# ELC0102_-_Red_Digits.net
KiCad netlist of a schematic drawn in Altium Designer
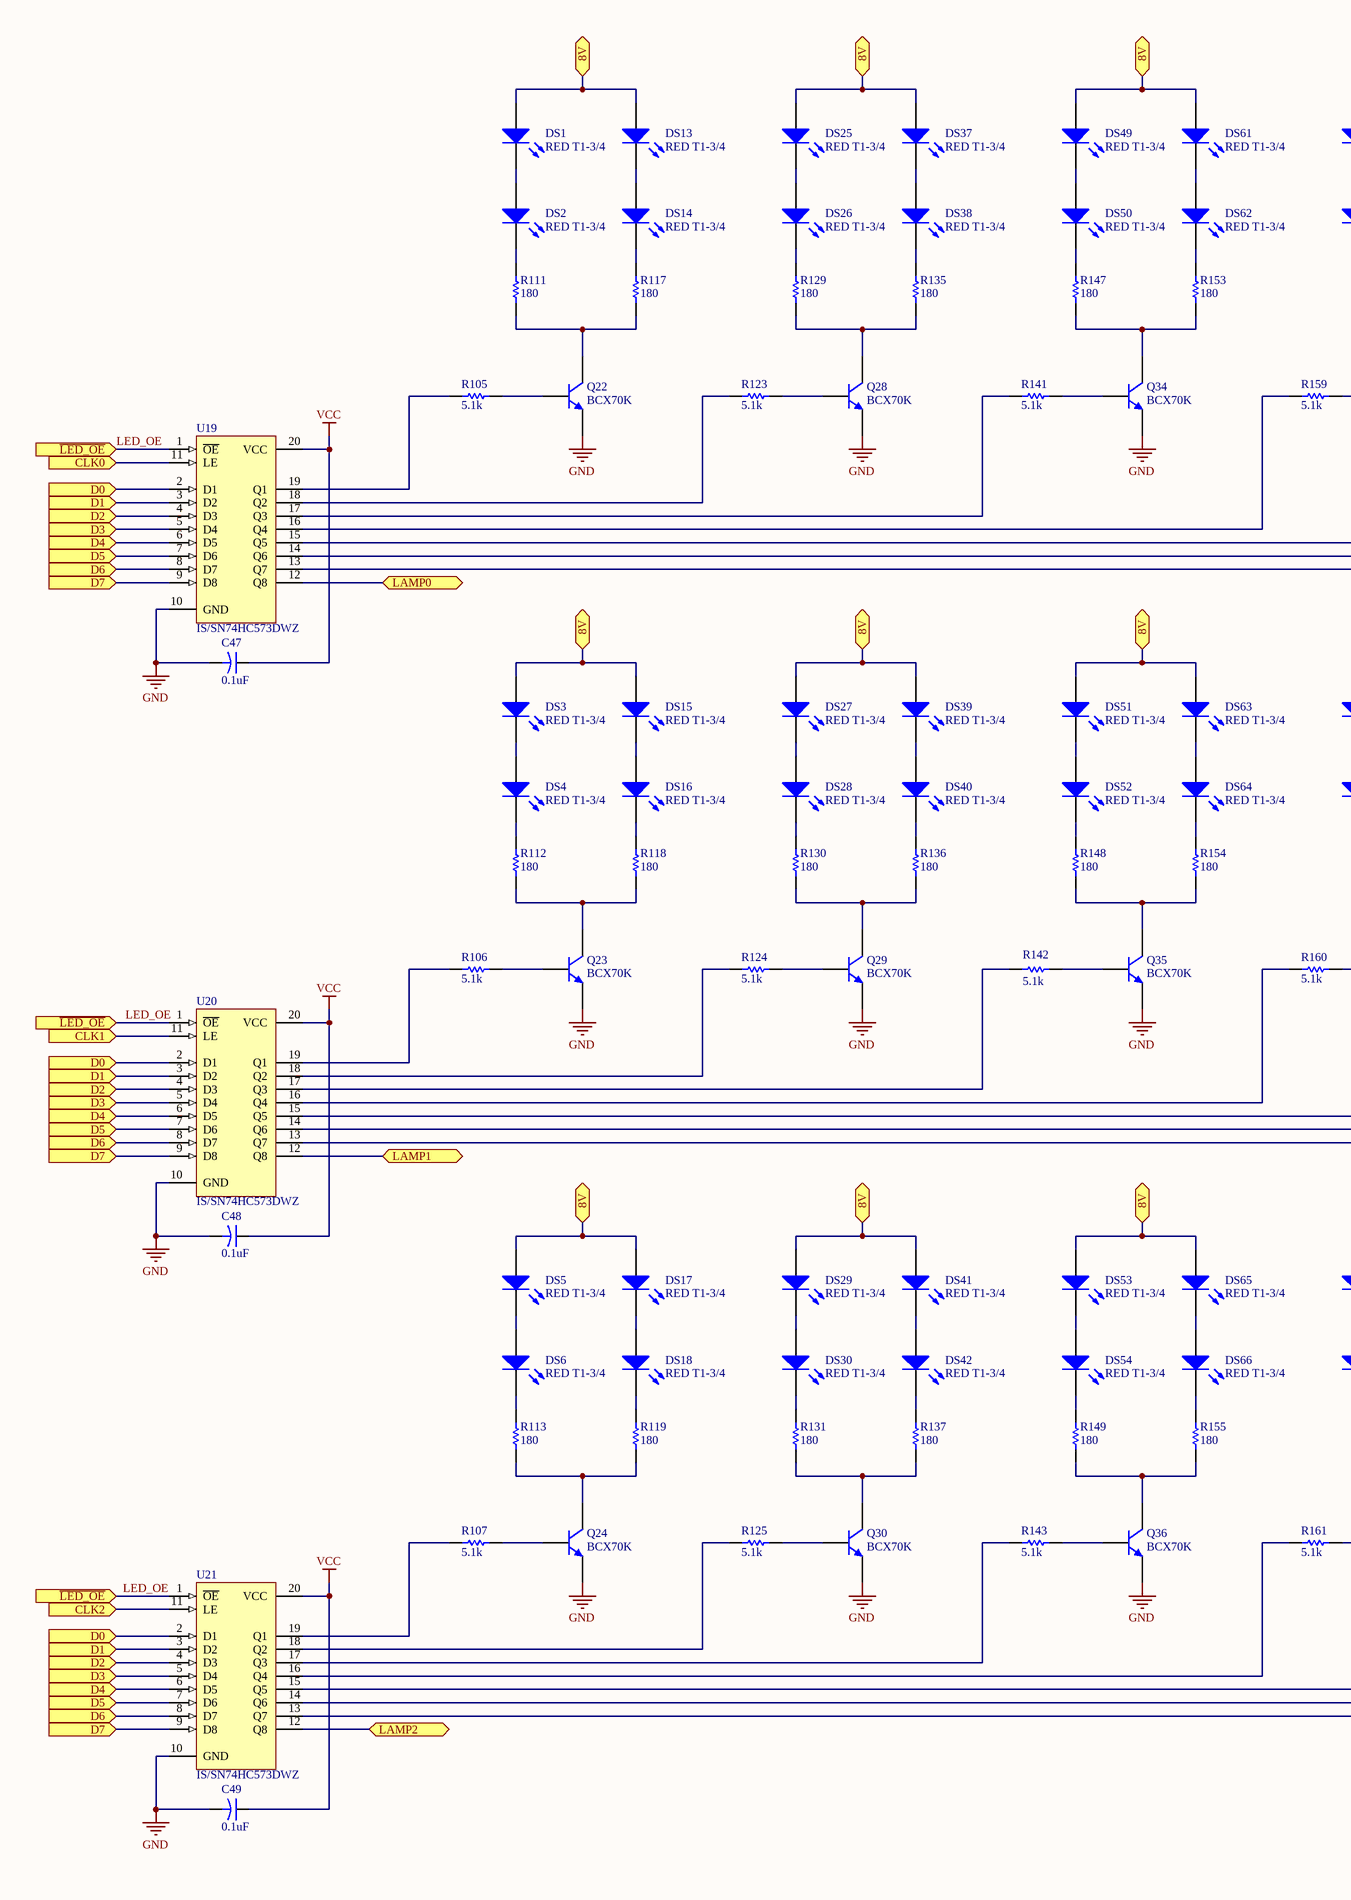
[diagram p0: ELC0102 - Red Digits.SchDoc, left]
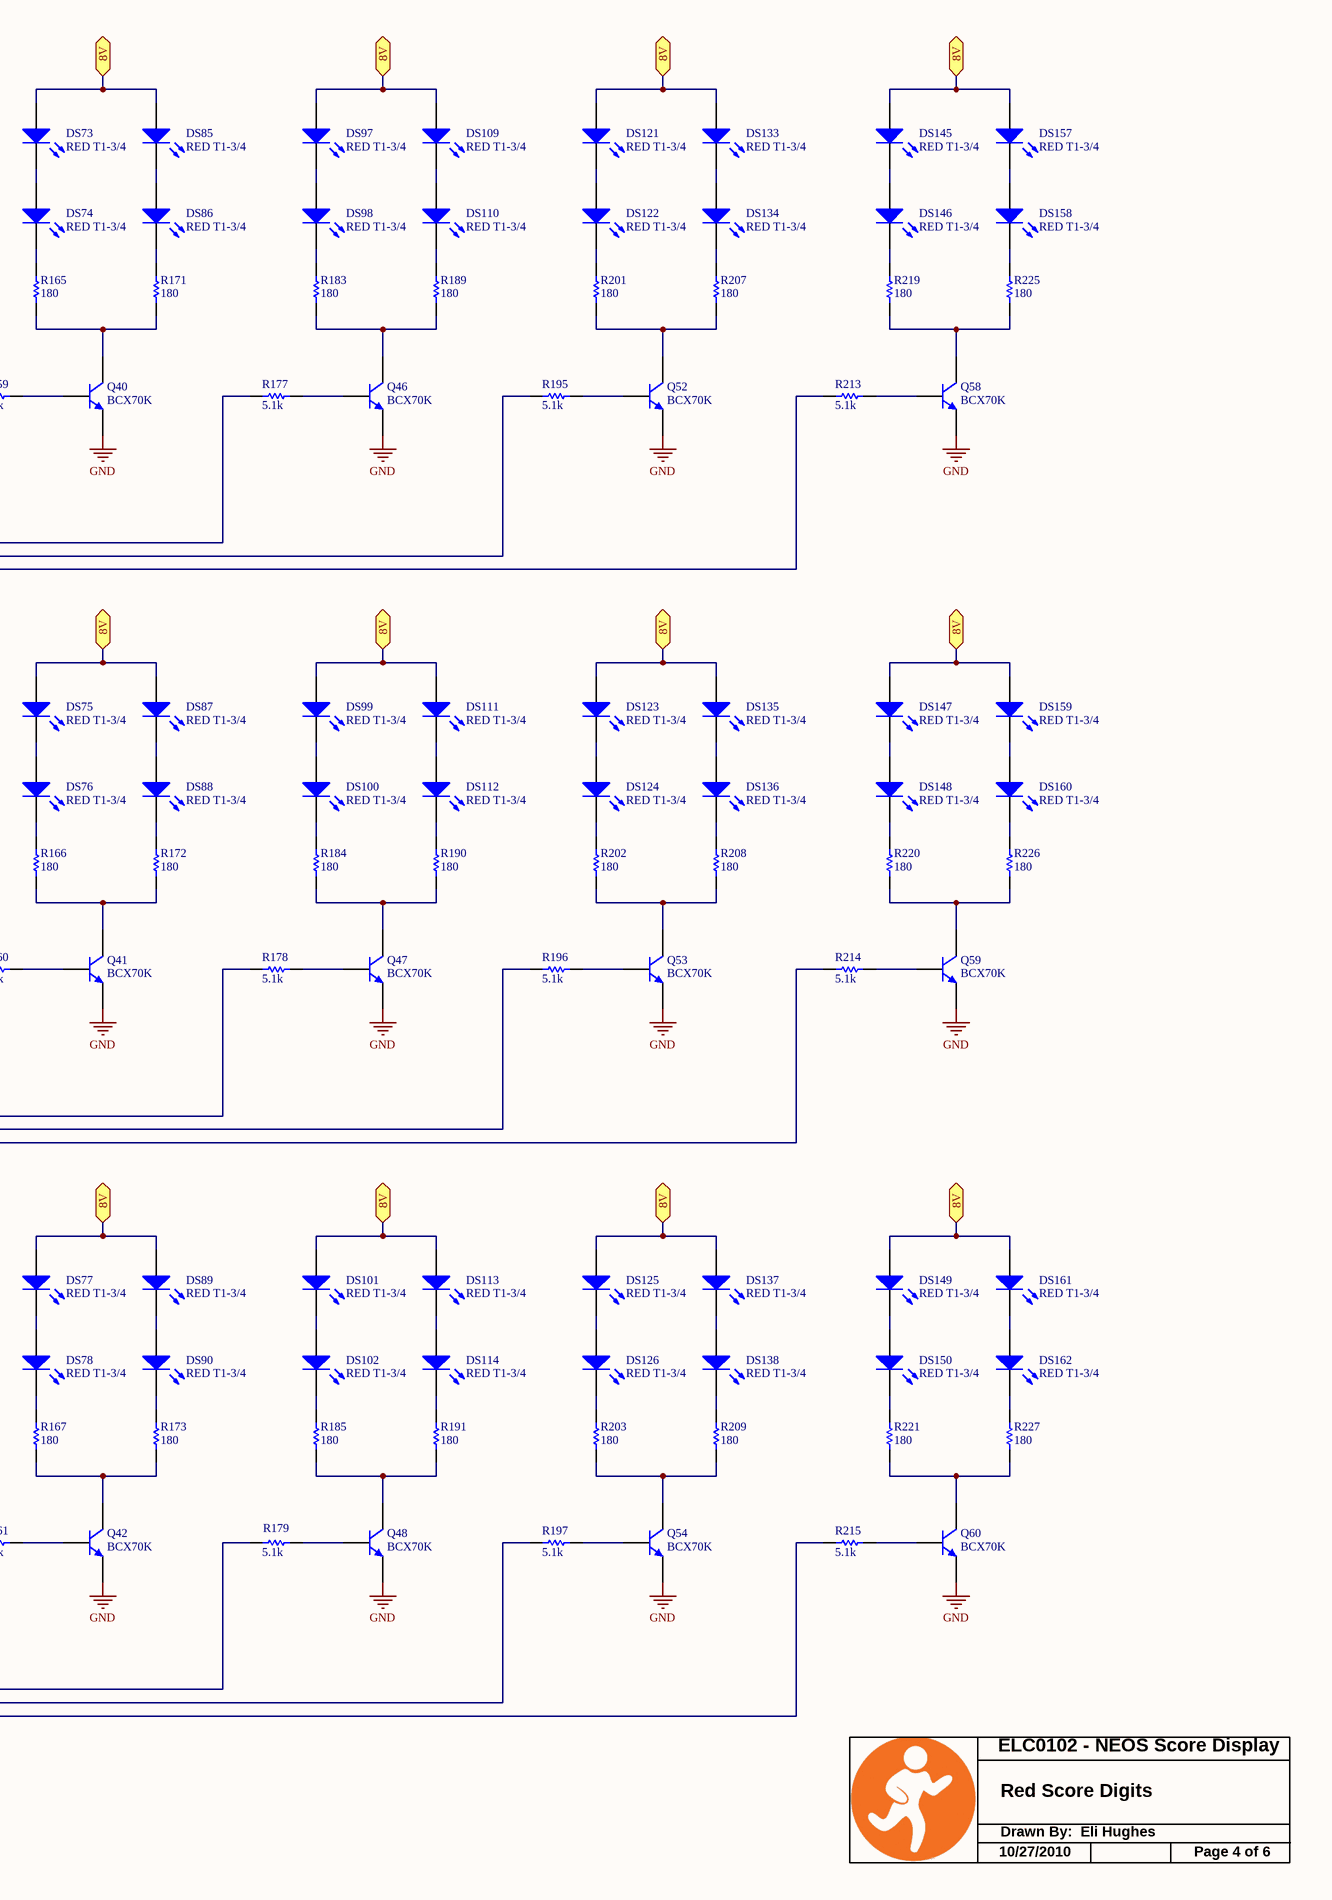
[diagram p1: ELC0102 - Red Digits.SchDoc, right]

(export (version "E")
  (design (tool "Eeschema 10.0.6"))
  (components
    (comp (ref "C47")
      (value "0.1uF")
      (footprint "C0805")
      (description "CAP .10UF 50V CERAMIC X7R 0805")
      (fields
        (field (name "MANUFACTURER") "Kemet")
        (field (name "MANUFACTURER PART NUMBER") "C0805C104K5RACTU")
        (field (name "SOURCE") "Digikey")
      )
      (libsource (lib "ELC102 - Scoreboard") (part "CS/C0805C104K5RACK"))
    )
    (comp (ref "C48")
      (value "0.1uF")
      (footprint "C0805")
      (description "CAP .10UF 50V CERAMIC X7R 0805")
      (fields
        (field (name "MANUFACTURER") "Kemet")
        (field (name "MANUFACTURER PART NUMBER") "C0805C104K5RACTU")
        (field (name "SOURCE") "Digikey")
      )
      (libsource (lib "ELC102 - Scoreboard") (part "CS/C0805C104K5RACK"))
    )
    (comp (ref "C49")
      (value "0.1uF")
      (footprint "C0805")
      (description "CAP .10UF 50V CERAMIC X7R 0805")
      (fields
        (field (name "MANUFACTURER") "Kemet")
        (field (name "MANUFACTURER PART NUMBER") "C0805C104K5RACTU")
        (field (name "SOURCE") "Digikey")
      )
      (libsource (lib "ELC102 - Scoreboard") (part "CS/C0805C104K5RACK"))
    )
    (comp (ref "DS1")
      (value "RED T1-3/4")
      (footprint "LED T1-3/4 Flush")
      (description "Optek LED Red /Clear High Brightness T1-3/4")
      (fields
        (field (name "MANUFACTURER") "TT Electronics/Optek Technology")
        (field (name "MANUFACTURER PART NUMBER") "OVLFR3C7")
        (field (name "SOURCE") "Digikey")
      )
      (libsource (lib "ScoreBoard") (part "LRCOVLFR3C7Z"))
    )
    (comp (ref "DS2")
      (value "RED T1-3/4")
      (footprint "LED T1-3/4 Flush")
      (description "Optek LED Red /Clear High Brightness T1-3/4")
      (fields
        (field (name "MANUFACTURER") "TT Electronics/Optek Technology")
        (field (name "MANUFACTURER PART NUMBER") "OVLFR3C7")
        (field (name "SOURCE") "Digikey")
      )
      (libsource (lib "ScoreBoard") (part "LRCOVLFR3C7Z"))
    )
    (comp (ref "DS3")
      (value "RED T1-3/4")
      (footprint "LED T1-3/4 Flush")
      (description "Optek LED Red /Clear High Brightness T1-3/4")
      (fields
        (field (name "MANUFACTURER") "TT Electronics/Optek Technology")
        (field (name "MANUFACTURER PART NUMBER") "OVLFR3C7")
        (field (name "SOURCE") "Digikey")
      )
      (libsource (lib "ScoreBoard") (part "LRCOVLFR3C7Z"))
    )
    (comp (ref "DS4")
      (value "RED T1-3/4")
      (footprint "LED T1-3/4 Flush")
      (description "Optek LED Red /Clear High Brightness T1-3/4")
      (fields
        (field (name "MANUFACTURER") "TT Electronics/Optek Technology")
        (field (name "MANUFACTURER PART NUMBER") "OVLFR3C7")
        (field (name "SOURCE") "Digikey")
      )
      (libsource (lib "ScoreBoard") (part "LRCOVLFR3C7Z"))
    )
    (comp (ref "DS5")
      (value "RED T1-3/4")
      (footprint "LED T1-3/4 Flush")
      (description "Optek LED Red /Clear High Brightness T1-3/4")
      (fields
        (field (name "MANUFACTURER") "TT Electronics/Optek Technology")
        (field (name "MANUFACTURER PART NUMBER") "OVLFR3C7")
        (field (name "SOURCE") "Digikey")
      )
      (libsource (lib "ScoreBoard") (part "LRCOVLFR3C7Z"))
    )
    (comp (ref "DS6")
      (value "RED T1-3/4")
      (footprint "LED T1-3/4 Flush")
      (description "Optek LED Red /Clear High Brightness T1-3/4")
      (fields
        (field (name "MANUFACTURER") "TT Electronics/Optek Technology")
        (field (name "MANUFACTURER PART NUMBER") "OVLFR3C7")
        (field (name "SOURCE") "Digikey")
      )
      (libsource (lib "ScoreBoard") (part "LRCOVLFR3C7Z"))
    )
    (comp (ref "DS13")
      (value "RED T1-3/4")
      (footprint "LED T1-3/4 Flush")
      (description "Optek LED Red /Clear High Brightness T1-3/4")
      (fields
        (field (name "MANUFACTURER") "TT Electronics/Optek Technology")
        (field (name "MANUFACTURER PART NUMBER") "OVLFR3C7")
        (field (name "SOURCE") "Digikey")
      )
      (libsource (lib "ScoreBoard") (part "LRCOVLFR3C7Z"))
    )
    (comp (ref "DS14")
      (value "RED T1-3/4")
      (footprint "LED T1-3/4 Flush")
      (description "Optek LED Red /Clear High Brightness T1-3/4")
      (fields
        (field (name "MANUFACTURER") "TT Electronics/Optek Technology")
        (field (name "MANUFACTURER PART NUMBER") "OVLFR3C7")
        (field (name "SOURCE") "Digikey")
      )
      (libsource (lib "ScoreBoard") (part "LRCOVLFR3C7Z"))
    )
    (comp (ref "DS15")
      (value "RED T1-3/4")
      (footprint "LED T1-3/4 Flush")
      (description "Optek LED Red /Clear High Brightness T1-3/4")
      (fields
        (field (name "MANUFACTURER") "TT Electronics/Optek Technology")
        (field (name "MANUFACTURER PART NUMBER") "OVLFR3C7")
        (field (name "SOURCE") "Digikey")
      )
      (libsource (lib "ScoreBoard") (part "LRCOVLFR3C7Z"))
    )
    (comp (ref "DS16")
      (value "RED T1-3/4")
      (footprint "LED T1-3/4 Flush")
      (description "Optek LED Red /Clear High Brightness T1-3/4")
      (fields
        (field (name "MANUFACTURER") "TT Electronics/Optek Technology")
        (field (name "MANUFACTURER PART NUMBER") "OVLFR3C7")
        (field (name "SOURCE") "Digikey")
      )
      (libsource (lib "ScoreBoard") (part "LRCOVLFR3C7Z"))
    )
    (comp (ref "DS17")
      (value "RED T1-3/4")
      (footprint "LED T1-3/4 Flush")
      (description "Optek LED Red /Clear High Brightness T1-3/4")
      (fields
        (field (name "MANUFACTURER") "TT Electronics/Optek Technology")
        (field (name "MANUFACTURER PART NUMBER") "OVLFR3C7")
        (field (name "SOURCE") "Digikey")
      )
      (libsource (lib "ScoreBoard") (part "LRCOVLFR3C7Z"))
    )
    (comp (ref "DS18")
      (value "RED T1-3/4")
      (footprint "LED T1-3/4 Flush")
      (description "Optek LED Red /Clear High Brightness T1-3/4")
      (fields
        (field (name "MANUFACTURER") "TT Electronics/Optek Technology")
        (field (name "MANUFACTURER PART NUMBER") "OVLFR3C7")
        (field (name "SOURCE") "Digikey")
      )
      (libsource (lib "ScoreBoard") (part "LRCOVLFR3C7Z"))
    )
    (comp (ref "DS25")
      (value "RED T1-3/4")
      (footprint "LED T1-3/4 Flush")
      (description "Optek LED Red /Clear High Brightness T1-3/4")
      (fields
        (field (name "MANUFACTURER") "TT Electronics/Optek Technology")
        (field (name "MANUFACTURER PART NUMBER") "OVLFR3C7")
        (field (name "SOURCE") "Digikey")
      )
      (libsource (lib "ScoreBoard") (part "LRCOVLFR3C7Z"))
    )
    (comp (ref "DS26")
      (value "RED T1-3/4")
      (footprint "LED T1-3/4 Flush")
      (description "Optek LED Red /Clear High Brightness T1-3/4")
      (fields
        (field (name "MANUFACTURER") "TT Electronics/Optek Technology")
        (field (name "MANUFACTURER PART NUMBER") "OVLFR3C7")
        (field (name "SOURCE") "Digikey")
      )
      (libsource (lib "ScoreBoard") (part "LRCOVLFR3C7Z"))
    )
    (comp (ref "DS27")
      (value "RED T1-3/4")
      (footprint "LED T1-3/4 Flush")
      (description "Optek LED Red /Clear High Brightness T1-3/4")
      (fields
        (field (name "MANUFACTURER") "TT Electronics/Optek Technology")
        (field (name "MANUFACTURER PART NUMBER") "OVLFR3C7")
        (field (name "SOURCE") "Digikey")
      )
      (libsource (lib "ScoreBoard") (part "LRCOVLFR3C7Z"))
    )
    (comp (ref "DS28")
      (value "RED T1-3/4")
      (footprint "LED T1-3/4 Flush")
      (description "Optek LED Red /Clear High Brightness T1-3/4")
      (fields
        (field (name "MANUFACTURER") "TT Electronics/Optek Technology")
        (field (name "MANUFACTURER PART NUMBER") "OVLFR3C7")
        (field (name "SOURCE") "Digikey")
      )
      (libsource (lib "ScoreBoard") (part "LRCOVLFR3C7Z"))
    )
    (comp (ref "DS29")
      (value "RED T1-3/4")
      (footprint "LED T1-3/4 Flush")
      (description "Optek LED Red /Clear High Brightness T1-3/4")
      (fields
        (field (name "MANUFACTURER") "TT Electronics/Optek Technology")
        (field (name "MANUFACTURER PART NUMBER") "OVLFR3C7")
        (field (name "SOURCE") "Digikey")
      )
      (libsource (lib "ScoreBoard") (part "LRCOVLFR3C7Z"))
    )
    (comp (ref "DS30")
      (value "RED T1-3/4")
      (footprint "LED T1-3/4 Flush")
      (description "Optek LED Red /Clear High Brightness T1-3/4")
      (fields
        (field (name "MANUFACTURER") "TT Electronics/Optek Technology")
        (field (name "MANUFACTURER PART NUMBER") "OVLFR3C7")
        (field (name "SOURCE") "Digikey")
      )
      (libsource (lib "ScoreBoard") (part "LRCOVLFR3C7Z"))
    )
    (comp (ref "DS37")
      (value "RED T1-3/4")
      (footprint "LED T1-3/4 Flush")
      (description "Optek LED Red /Clear High Brightness T1-3/4")
      (fields
        (field (name "MANUFACTURER") "TT Electronics/Optek Technology")
        (field (name "MANUFACTURER PART NUMBER") "OVLFR3C7")
        (field (name "SOURCE") "Digikey")
      )
      (libsource (lib "ScoreBoard") (part "LRCOVLFR3C7Z"))
    )
    (comp (ref "DS38")
      (value "RED T1-3/4")
      (footprint "LED T1-3/4 Flush")
      (description "Optek LED Red /Clear High Brightness T1-3/4")
      (fields
        (field (name "MANUFACTURER") "TT Electronics/Optek Technology")
        (field (name "MANUFACTURER PART NUMBER") "OVLFR3C7")
        (field (name "SOURCE") "Digikey")
      )
      (libsource (lib "ScoreBoard") (part "LRCOVLFR3C7Z"))
    )
    (comp (ref "DS39")
      (value "RED T1-3/4")
      (footprint "LED T1-3/4 Flush")
      (description "Optek LED Red /Clear High Brightness T1-3/4")
      (fields
        (field (name "MANUFACTURER") "TT Electronics/Optek Technology")
        (field (name "MANUFACTURER PART NUMBER") "OVLFR3C7")
        (field (name "SOURCE") "Digikey")
      )
      (libsource (lib "ScoreBoard") (part "LRCOVLFR3C7Z"))
    )
    (comp (ref "DS40")
      (value "RED T1-3/4")
      (footprint "LED T1-3/4 Flush")
      (description "Optek LED Red /Clear High Brightness T1-3/4")
      (fields
        (field (name "MANUFACTURER") "TT Electronics/Optek Technology")
        (field (name "MANUFACTURER PART NUMBER") "OVLFR3C7")
        (field (name "SOURCE") "Digikey")
      )
      (libsource (lib "ScoreBoard") (part "LRCOVLFR3C7Z"))
    )
    (comp (ref "DS41")
      (value "RED T1-3/4")
      (footprint "LED T1-3/4 Flush")
      (description "Optek LED Red /Clear High Brightness T1-3/4")
      (fields
        (field (name "MANUFACTURER") "TT Electronics/Optek Technology")
        (field (name "MANUFACTURER PART NUMBER") "OVLFR3C7")
        (field (name "SOURCE") "Digikey")
      )
      (libsource (lib "ScoreBoard") (part "LRCOVLFR3C7Z"))
    )
    (comp (ref "DS42")
      (value "RED T1-3/4")
      (footprint "LED T1-3/4 Flush")
      (description "Optek LED Red /Clear High Brightness T1-3/4")
      (fields
        (field (name "MANUFACTURER") "TT Electronics/Optek Technology")
        (field (name "MANUFACTURER PART NUMBER") "OVLFR3C7")
        (field (name "SOURCE") "Digikey")
      )
      (libsource (lib "ScoreBoard") (part "LRCOVLFR3C7Z"))
    )
    (comp (ref "DS49")
      (value "RED T1-3/4")
      (footprint "LED T1-3/4 Flush")
      (description "Optek LED Red /Clear High Brightness T1-3/4")
      (fields
        (field (name "MANUFACTURER") "TT Electronics/Optek Technology")
        (field (name "MANUFACTURER PART NUMBER") "OVLFR3C7")
        (field (name "SOURCE") "Digikey")
      )
      (libsource (lib "ScoreBoard") (part "LRCOVLFR3C7Z"))
    )
    (comp (ref "DS50")
      (value "RED T1-3/4")
      (footprint "LED T1-3/4 Flush")
      (description "Optek LED Red /Clear High Brightness T1-3/4")
      (fields
        (field (name "MANUFACTURER") "TT Electronics/Optek Technology")
        (field (name "MANUFACTURER PART NUMBER") "OVLFR3C7")
        (field (name "SOURCE") "Digikey")
      )
      (libsource (lib "ScoreBoard") (part "LRCOVLFR3C7Z"))
    )
    (comp (ref "DS51")
      (value "RED T1-3/4")
      (footprint "LED T1-3/4 Flush")
      (description "Optek LED Red /Clear High Brightness T1-3/4")
      (fields
        (field (name "MANUFACTURER") "TT Electronics/Optek Technology")
        (field (name "MANUFACTURER PART NUMBER") "OVLFR3C7")
        (field (name "SOURCE") "Digikey")
      )
      (libsource (lib "ScoreBoard") (part "LRCOVLFR3C7Z"))
    )
    (comp (ref "DS52")
      (value "RED T1-3/4")
      (footprint "LED T1-3/4 Flush")
      (description "Optek LED Red /Clear High Brightness T1-3/4")
      (fields
        (field (name "MANUFACTURER") "TT Electronics/Optek Technology")
        (field (name "MANUFACTURER PART NUMBER") "OVLFR3C7")
        (field (name "SOURCE") "Digikey")
      )
      (libsource (lib "ScoreBoard") (part "LRCOVLFR3C7Z"))
    )
    (comp (ref "DS53")
      (value "RED T1-3/4")
      (footprint "LED T1-3/4 Flush")
      (description "Optek LED Red /Clear High Brightness T1-3/4")
      (fields
        (field (name "MANUFACTURER") "TT Electronics/Optek Technology")
        (field (name "MANUFACTURER PART NUMBER") "OVLFR3C7")
        (field (name "SOURCE") "Digikey")
      )
      (libsource (lib "ScoreBoard") (part "LRCOVLFR3C7Z"))
    )
    (comp (ref "DS54")
      (value "RED T1-3/4")
      (footprint "LED T1-3/4 Flush")
      (description "Optek LED Red /Clear High Brightness T1-3/4")
      (fields
        (field (name "MANUFACTURER") "TT Electronics/Optek Technology")
        (field (name "MANUFACTURER PART NUMBER") "OVLFR3C7")
        (field (name "SOURCE") "Digikey")
      )
      (libsource (lib "ScoreBoard") (part "LRCOVLFR3C7Z"))
    )
    (comp (ref "DS61")
      (value "RED T1-3/4")
      (footprint "LED T1-3/4 Flush")
      (description "Optek LED Red /Clear High Brightness T1-3/4")
      (fields
        (field (name "MANUFACTURER") "TT Electronics/Optek Technology")
        (field (name "MANUFACTURER PART NUMBER") "OVLFR3C7")
        (field (name "SOURCE") "Digikey")
      )
      (libsource (lib "ScoreBoard") (part "LRCOVLFR3C7Z"))
    )
    (comp (ref "DS62")
      (value "RED T1-3/4")
      (footprint "LED T1-3/4 Flush")
      (description "Optek LED Red /Clear High Brightness T1-3/4")
      (fields
        (field (name "MANUFACTURER") "TT Electronics/Optek Technology")
        (field (name "MANUFACTURER PART NUMBER") "OVLFR3C7")
        (field (name "SOURCE") "Digikey")
      )
      (libsource (lib "ScoreBoard") (part "LRCOVLFR3C7Z"))
    )
    (comp (ref "DS63")
      (value "RED T1-3/4")
      (footprint "LED T1-3/4 Flush")
      (description "Optek LED Red /Clear High Brightness T1-3/4")
      (fields
        (field (name "MANUFACTURER") "TT Electronics/Optek Technology")
        (field (name "MANUFACTURER PART NUMBER") "OVLFR3C7")
        (field (name "SOURCE") "Digikey")
      )
      (libsource (lib "ScoreBoard") (part "LRCOVLFR3C7Z"))
    )
    (comp (ref "DS64")
      (value "RED T1-3/4")
      (footprint "LED T1-3/4 Flush")
      (description "Optek LED Red /Clear High Brightness T1-3/4")
      (fields
        (field (name "MANUFACTURER") "TT Electronics/Optek Technology")
        (field (name "MANUFACTURER PART NUMBER") "OVLFR3C7")
        (field (name "SOURCE") "Digikey")
      )
      (libsource (lib "ScoreBoard") (part "LRCOVLFR3C7Z"))
    )
    (comp (ref "DS65")
      (value "RED T1-3/4")
      (footprint "LED T1-3/4 Flush")
      (description "Optek LED Red /Clear High Brightness T1-3/4")
      (fields
        (field (name "MANUFACTURER") "TT Electronics/Optek Technology")
        (field (name "MANUFACTURER PART NUMBER") "OVLFR3C7")
        (field (name "SOURCE") "Digikey")
      )
      (libsource (lib "ScoreBoard") (part "LRCOVLFR3C7Z"))
    )
    (comp (ref "DS66")
      (value "RED T1-3/4")
      (footprint "LED T1-3/4 Flush")
      (description "Optek LED Red /Clear High Brightness T1-3/4")
      (fields
        (field (name "MANUFACTURER") "TT Electronics/Optek Technology")
        (field (name "MANUFACTURER PART NUMBER") "OVLFR3C7")
        (field (name "SOURCE") "Digikey")
      )
      (libsource (lib "ScoreBoard") (part "LRCOVLFR3C7Z"))
    )
    (comp (ref "DS73")
      (value "RED T1-3/4")
      (footprint "LED T1-3/4 Flush")
      (description "Optek LED Red /Clear High Brightness T1-3/4")
      (fields
        (field (name "MANUFACTURER") "TT Electronics/Optek Technology")
        (field (name "MANUFACTURER PART NUMBER") "OVLFR3C7")
        (field (name "SOURCE") "Digikey")
      )
      (libsource (lib "ScoreBoard") (part "LRCOVLFR3C7Z"))
    )
    (comp (ref "DS74")
      (value "RED T1-3/4")
      (footprint "LED T1-3/4 Flush")
      (description "Optek LED Red /Clear High Brightness T1-3/4")
      (fields
        (field (name "MANUFACTURER") "TT Electronics/Optek Technology")
        (field (name "MANUFACTURER PART NUMBER") "OVLFR3C7")
        (field (name "SOURCE") "Digikey")
      )
      (libsource (lib "ScoreBoard") (part "LRCOVLFR3C7Z"))
    )
    (comp (ref "DS75")
      (value "RED T1-3/4")
      (footprint "LED T1-3/4 Flush")
      (description "Optek LED Red /Clear High Brightness T1-3/4")
      (fields
        (field (name "MANUFACTURER") "TT Electronics/Optek Technology")
        (field (name "MANUFACTURER PART NUMBER") "OVLFR3C7")
        (field (name "SOURCE") "Digikey")
      )
      (libsource (lib "ScoreBoard") (part "LRCOVLFR3C7Z"))
    )
    (comp (ref "DS76")
      (value "RED T1-3/4")
      (footprint "LED T1-3/4 Flush")
      (description "Optek LED Red /Clear High Brightness T1-3/4")
      (fields
        (field (name "MANUFACTURER") "TT Electronics/Optek Technology")
        (field (name "MANUFACTURER PART NUMBER") "OVLFR3C7")
        (field (name "SOURCE") "Digikey")
      )
      (libsource (lib "ScoreBoard") (part "LRCOVLFR3C7Z"))
    )
    (comp (ref "DS77")
      (value "RED T1-3/4")
      (footprint "LED T1-3/4 Flush")
      (description "Optek LED Red /Clear High Brightness T1-3/4")
      (fields
        (field (name "MANUFACTURER") "TT Electronics/Optek Technology")
        (field (name "MANUFACTURER PART NUMBER") "OVLFR3C7")
        (field (name "SOURCE") "Digikey")
      )
      (libsource (lib "ScoreBoard") (part "LRCOVLFR3C7Z"))
    )
    (comp (ref "DS78")
      (value "RED T1-3/4")
      (footprint "LED T1-3/4 Flush")
      (description "Optek LED Red /Clear High Brightness T1-3/4")
      (fields
        (field (name "MANUFACTURER") "TT Electronics/Optek Technology")
        (field (name "MANUFACTURER PART NUMBER") "OVLFR3C7")
        (field (name "SOURCE") "Digikey")
      )
      (libsource (lib "ScoreBoard") (part "LRCOVLFR3C7Z"))
    )
    (comp (ref "DS85")
      (value "RED T1-3/4")
      (footprint "LED T1-3/4 Flush")
      (description "Optek LED Red /Clear High Brightness T1-3/4")
      (fields
        (field (name "MANUFACTURER") "TT Electronics/Optek Technology")
        (field (name "MANUFACTURER PART NUMBER") "OVLFR3C7")
        (field (name "SOURCE") "Digikey")
      )
      (libsource (lib "ScoreBoard") (part "LRCOVLFR3C7Z"))
    )
    (comp (ref "DS86")
      (value "RED T1-3/4")
      (footprint "LED T1-3/4 Flush")
      (description "Optek LED Red /Clear High Brightness T1-3/4")
      (fields
        (field (name "MANUFACTURER") "TT Electronics/Optek Technology")
        (field (name "MANUFACTURER PART NUMBER") "OVLFR3C7")
        (field (name "SOURCE") "Digikey")
      )
      (libsource (lib "ScoreBoard") (part "LRCOVLFR3C7Z"))
    )
    (comp (ref "DS87")
      (value "RED T1-3/4")
      (footprint "LED T1-3/4 Flush")
      (description "Optek LED Red /Clear High Brightness T1-3/4")
      (fields
        (field (name "MANUFACTURER") "TT Electronics/Optek Technology")
        (field (name "MANUFACTURER PART NUMBER") "OVLFR3C7")
        (field (name "SOURCE") "Digikey")
      )
      (libsource (lib "ScoreBoard") (part "LRCOVLFR3C7Z"))
    )
    (comp (ref "DS88")
      (value "RED T1-3/4")
      (footprint "LED T1-3/4 Flush")
      (description "Optek LED Red /Clear High Brightness T1-3/4")
      (fields
        (field (name "MANUFACTURER") "TT Electronics/Optek Technology")
        (field (name "MANUFACTURER PART NUMBER") "OVLFR3C7")
        (field (name "SOURCE") "Digikey")
      )
      (libsource (lib "ScoreBoard") (part "LRCOVLFR3C7Z"))
    )
    (comp (ref "DS89")
      (value "RED T1-3/4")
      (footprint "LED T1-3/4 Flush")
      (description "Optek LED Red /Clear High Brightness T1-3/4")
      (fields
        (field (name "MANUFACTURER") "TT Electronics/Optek Technology")
        (field (name "MANUFACTURER PART NUMBER") "OVLFR3C7")
        (field (name "SOURCE") "Digikey")
      )
      (libsource (lib "ScoreBoard") (part "LRCOVLFR3C7Z"))
    )
    (comp (ref "DS90")
      (value "RED T1-3/4")
      (footprint "LED T1-3/4 Flush")
      (description "Optek LED Red /Clear High Brightness T1-3/4")
      (fields
        (field (name "MANUFACTURER") "TT Electronics/Optek Technology")
        (field (name "MANUFACTURER PART NUMBER") "OVLFR3C7")
        (field (name "SOURCE") "Digikey")
      )
      (libsource (lib "ScoreBoard") (part "LRCOVLFR3C7Z"))
    )
    (comp (ref "DS97")
      (value "RED T1-3/4")
      (footprint "LED T1-3/4 Flush")
      (description "Optek LED Red /Clear High Brightness T1-3/4")
      (fields
        (field (name "MANUFACTURER") "TT Electronics/Optek Technology")
        (field (name "MANUFACTURER PART NUMBER") "OVLFR3C7")
        (field (name "SOURCE") "Digikey")
      )
      (libsource (lib "ScoreBoard") (part "LRCOVLFR3C7Z"))
    )
    (comp (ref "DS98")
      (value "RED T1-3/4")
      (footprint "LED T1-3/4 Flush")
      (description "Optek LED Red /Clear High Brightness T1-3/4")
      (fields
        (field (name "MANUFACTURER") "TT Electronics/Optek Technology")
        (field (name "MANUFACTURER PART NUMBER") "OVLFR3C7")
        (field (name "SOURCE") "Digikey")
      )
      (libsource (lib "ScoreBoard") (part "LRCOVLFR3C7Z"))
    )
    (comp (ref "DS99")
      (value "RED T1-3/4")
      (footprint "LED T1-3/4 Flush")
      (description "Optek LED Red /Clear High Brightness T1-3/4")
      (fields
        (field (name "MANUFACTURER") "TT Electronics/Optek Technology")
        (field (name "MANUFACTURER PART NUMBER") "OVLFR3C7")
        (field (name "SOURCE") "Digikey")
      )
      (libsource (lib "ScoreBoard") (part "LRCOVLFR3C7Z"))
    )
    (comp (ref "DS100")
      (value "RED T1-3/4")
      (footprint "LED T1-3/4 Flush")
      (description "Optek LED Red /Clear High Brightness T1-3/4")
      (fields
        (field (name "MANUFACTURER") "TT Electronics/Optek Technology")
        (field (name "MANUFACTURER PART NUMBER") "OVLFR3C7")
        (field (name "SOURCE") "Digikey")
      )
      (libsource (lib "ScoreBoard") (part "LRCOVLFR3C7Z"))
    )
    (comp (ref "DS101")
      (value "RED T1-3/4")
      (footprint "LED T1-3/4 Flush")
      (description "Optek LED Red /Clear High Brightness T1-3/4")
      (fields
        (field (name "MANUFACTURER") "TT Electronics/Optek Technology")
        (field (name "MANUFACTURER PART NUMBER") "OVLFR3C7")
        (field (name "SOURCE") "Digikey")
      )
      (libsource (lib "ScoreBoard") (part "LRCOVLFR3C7Z"))
    )
    (comp (ref "DS102")
      (value "RED T1-3/4")
      (footprint "LED T1-3/4 Flush")
      (description "Optek LED Red /Clear High Brightness T1-3/4")
      (fields
        (field (name "MANUFACTURER") "TT Electronics/Optek Technology")
        (field (name "MANUFACTURER PART NUMBER") "OVLFR3C7")
        (field (name "SOURCE") "Digikey")
      )
      (libsource (lib "ScoreBoard") (part "LRCOVLFR3C7Z"))
    )
    (comp (ref "DS109")
      (value "RED T1-3/4")
      (footprint "LED T1-3/4 Flush")
      (description "Optek LED Red /Clear High Brightness T1-3/4")
      (fields
        (field (name "MANUFACTURER") "TT Electronics/Optek Technology")
        (field (name "MANUFACTURER PART NUMBER") "OVLFR3C7")
        (field (name "SOURCE") "Digikey")
      )
      (libsource (lib "ScoreBoard") (part "LRCOVLFR3C7Z"))
    )
    (comp (ref "DS110")
      (value "RED T1-3/4")
      (footprint "LED T1-3/4 Flush")
      (description "Optek LED Red /Clear High Brightness T1-3/4")
      (fields
        (field (name "MANUFACTURER") "TT Electronics/Optek Technology")
        (field (name "MANUFACTURER PART NUMBER") "OVLFR3C7")
        (field (name "SOURCE") "Digikey")
      )
      (libsource (lib "ScoreBoard") (part "LRCOVLFR3C7Z"))
    )
    (comp (ref "DS111")
      (value "RED T1-3/4")
      (footprint "LED T1-3/4 Flush")
      (description "Optek LED Red /Clear High Brightness T1-3/4")
      (fields
        (field (name "MANUFACTURER") "TT Electronics/Optek Technology")
        (field (name "MANUFACTURER PART NUMBER") "OVLFR3C7")
        (field (name "SOURCE") "Digikey")
      )
      (libsource (lib "ScoreBoard") (part "LRCOVLFR3C7Z"))
    )
    (comp (ref "DS112")
      (value "RED T1-3/4")
      (footprint "LED T1-3/4 Flush")
      (description "Optek LED Red /Clear High Brightness T1-3/4")
      (fields
        (field (name "MANUFACTURER") "TT Electronics/Optek Technology")
        (field (name "MANUFACTURER PART NUMBER") "OVLFR3C7")
        (field (name "SOURCE") "Digikey")
      )
      (libsource (lib "ScoreBoard") (part "LRCOVLFR3C7Z"))
    )
    (comp (ref "DS113")
      (value "RED T1-3/4")
      (footprint "LED T1-3/4 Flush")
      (description "Optek LED Red /Clear High Brightness T1-3/4")
      (fields
        (field (name "MANUFACTURER") "TT Electronics/Optek Technology")
        (field (name "MANUFACTURER PART NUMBER") "OVLFR3C7")
        (field (name "SOURCE") "Digikey")
      )
      (libsource (lib "ScoreBoard") (part "LRCOVLFR3C7Z"))
    )
    (comp (ref "DS114")
      (value "RED T1-3/4")
      (footprint "LED T1-3/4 Flush")
      (description "Optek LED Red /Clear High Brightness T1-3/4")
      (fields
        (field (name "MANUFACTURER") "TT Electronics/Optek Technology")
        (field (name "MANUFACTURER PART NUMBER") "OVLFR3C7")
        (field (name "SOURCE") "Digikey")
      )
      (libsource (lib "ScoreBoard") (part "LRCOVLFR3C7Z"))
    )
    (comp (ref "DS121")
      (value "RED T1-3/4")
      (footprint "LED T1-3/4 Flush")
      (description "Optek LED Red /Clear High Brightness T1-3/4")
      (fields
        (field (name "MANUFACTURER") "TT Electronics/Optek Technology")
        (field (name "MANUFACTURER PART NUMBER") "OVLFR3C7")
        (field (name "SOURCE") "Digikey")
      )
      (libsource (lib "ScoreBoard") (part "LRCOVLFR3C7Z"))
    )
    (comp (ref "DS122")
      (value "RED T1-3/4")
      (footprint "LED T1-3/4 Flush")
      (description "Optek LED Red /Clear High Brightness T1-3/4")
      (fields
        (field (name "MANUFACTURER") "TT Electronics/Optek Technology")
        (field (name "MANUFACTURER PART NUMBER") "OVLFR3C7")
        (field (name "SOURCE") "Digikey")
      )
      (libsource (lib "ScoreBoard") (part "LRCOVLFR3C7Z"))
    )
    (comp (ref "DS123")
      (value "RED T1-3/4")
      (footprint "LED T1-3/4 Flush")
      (description "Optek LED Red /Clear High Brightness T1-3/4")
      (fields
        (field (name "MANUFACTURER") "TT Electronics/Optek Technology")
        (field (name "MANUFACTURER PART NUMBER") "OVLFR3C7")
        (field (name "SOURCE") "Digikey")
      )
      (libsource (lib "ScoreBoard") (part "LRCOVLFR3C7Z"))
    )
    (comp (ref "DS124")
      (value "RED T1-3/4")
      (footprint "LED T1-3/4 Flush")
      (description "Optek LED Red /Clear High Brightness T1-3/4")
      (fields
        (field (name "MANUFACTURER") "TT Electronics/Optek Technology")
        (field (name "MANUFACTURER PART NUMBER") "OVLFR3C7")
        (field (name "SOURCE") "Digikey")
      )
      (libsource (lib "ScoreBoard") (part "LRCOVLFR3C7Z"))
    )
    (comp (ref "DS125")
      (value "RED T1-3/4")
      (footprint "LED T1-3/4 Flush")
      (description "Optek LED Red /Clear High Brightness T1-3/4")
      (fields
        (field (name "MANUFACTURER") "TT Electronics/Optek Technology")
        (field (name "MANUFACTURER PART NUMBER") "OVLFR3C7")
        (field (name "SOURCE") "Digikey")
      )
      (libsource (lib "ScoreBoard") (part "LRCOVLFR3C7Z"))
    )
    (comp (ref "DS126")
      (value "RED T1-3/4")
      (footprint "LED T1-3/4 Flush")
      (description "Optek LED Red /Clear High Brightness T1-3/4")
      (fields
        (field (name "MANUFACTURER") "TT Electronics/Optek Technology")
        (field (name "MANUFACTURER PART NUMBER") "OVLFR3C7")
        (field (name "SOURCE") "Digikey")
      )
      (libsource (lib "ScoreBoard") (part "LRCOVLFR3C7Z"))
    )
    (comp (ref "DS133")
      (value "RED T1-3/4")
      (footprint "LED T1-3/4 Flush")
      (description "Optek LED Red /Clear High Brightness T1-3/4")
      (fields
        (field (name "MANUFACTURER") "TT Electronics/Optek Technology")
        (field (name "MANUFACTURER PART NUMBER") "OVLFR3C7")
        (field (name "SOURCE") "Digikey")
      )
      (libsource (lib "ScoreBoard") (part "LRCOVLFR3C7Z"))
    )
    (comp (ref "DS134")
      (value "RED T1-3/4")
      (footprint "LED T1-3/4 Flush")
      (description "Optek LED Red /Clear High Brightness T1-3/4")
      (fields
        (field (name "MANUFACTURER") "TT Electronics/Optek Technology")
        (field (name "MANUFACTURER PART NUMBER") "OVLFR3C7")
        (field (name "SOURCE") "Digikey")
      )
      (libsource (lib "ScoreBoard") (part "LRCOVLFR3C7Z"))
    )
    (comp (ref "DS135")
      (value "RED T1-3/4")
      (footprint "LED T1-3/4 Flush")
      (description "Optek LED Red /Clear High Brightness T1-3/4")
      (fields
        (field (name "MANUFACTURER") "TT Electronics/Optek Technology")
        (field (name "MANUFACTURER PART NUMBER") "OVLFR3C7")
        (field (name "SOURCE") "Digikey")
      )
      (libsource (lib "ScoreBoard") (part "LRCOVLFR3C7Z"))
    )
    (comp (ref "DS136")
      (value "RED T1-3/4")
      (footprint "LED T1-3/4 Flush")
      (description "Optek LED Red /Clear High Brightness T1-3/4")
      (fields
        (field (name "MANUFACTURER") "TT Electronics/Optek Technology")
        (field (name "MANUFACTURER PART NUMBER") "OVLFR3C7")
        (field (name "SOURCE") "Digikey")
      )
      (libsource (lib "ScoreBoard") (part "LRCOVLFR3C7Z"))
    )
    (comp (ref "DS137")
      (value "RED T1-3/4")
      (footprint "LED T1-3/4 Flush")
      (description "Optek LED Red /Clear High Brightness T1-3/4")
      (fields
        (field (name "MANUFACTURER") "TT Electronics/Optek Technology")
        (field (name "MANUFACTURER PART NUMBER") "OVLFR3C7")
        (field (name "SOURCE") "Digikey")
      )
      (libsource (lib "ScoreBoard") (part "LRCOVLFR3C7Z"))
    )
    (comp (ref "DS138")
      (value "RED T1-3/4")
      (footprint "LED T1-3/4 Flush")
      (description "Optek LED Red /Clear High Brightness T1-3/4")
      (fields
        (field (name "MANUFACTURER") "TT Electronics/Optek Technology")
        (field (name "MANUFACTURER PART NUMBER") "OVLFR3C7")
        (field (name "SOURCE") "Digikey")
      )
      (libsource (lib "ScoreBoard") (part "LRCOVLFR3C7Z"))
    )
    (comp (ref "DS145")
      (value "RED T1-3/4")
      (footprint "LED T1-3/4 Flush")
      (description "Optek LED Red /Clear High Brightness T1-3/4")
      (fields
        (field (name "MANUFACTURER") "TT Electronics/Optek Technology")
        (field (name "MANUFACTURER PART NUMBER") "OVLFR3C7")
        (field (name "SOURCE") "Digikey")
      )
      (libsource (lib "ScoreBoard") (part "LRCOVLFR3C7Z"))
    )
    (comp (ref "DS146")
      (value "RED T1-3/4")
      (footprint "LED T1-3/4 Flush")
      (description "Optek LED Red /Clear High Brightness T1-3/4")
      (fields
        (field (name "MANUFACTURER") "TT Electronics/Optek Technology")
        (field (name "MANUFACTURER PART NUMBER") "OVLFR3C7")
        (field (name "SOURCE") "Digikey")
      )
      (libsource (lib "ScoreBoard") (part "LRCOVLFR3C7Z"))
    )
    (comp (ref "DS147")
      (value "RED T1-3/4")
      (footprint "LED T1-3/4 Flush")
      (description "Optek LED Red /Clear High Brightness T1-3/4")
      (fields
        (field (name "MANUFACTURER") "TT Electronics/Optek Technology")
        (field (name "MANUFACTURER PART NUMBER") "OVLFR3C7")
        (field (name "SOURCE") "Digikey")
      )
      (libsource (lib "ScoreBoard") (part "LRCOVLFR3C7Z"))
    )
    (comp (ref "DS148")
      (value "RED T1-3/4")
      (footprint "LED T1-3/4 Flush")
      (description "Optek LED Red /Clear High Brightness T1-3/4")
      (fields
        (field (name "MANUFACTURER") "TT Electronics/Optek Technology")
        (field (name "MANUFACTURER PART NUMBER") "OVLFR3C7")
        (field (name "SOURCE") "Digikey")
      )
      (libsource (lib "ScoreBoard") (part "LRCOVLFR3C7Z"))
    )
    (comp (ref "DS149")
      (value "RED T1-3/4")
      (footprint "LED T1-3/4 Flush")
      (description "Optek LED Red /Clear High Brightness T1-3/4")
      (fields
        (field (name "MANUFACTURER") "TT Electronics/Optek Technology")
        (field (name "MANUFACTURER PART NUMBER") "OVLFR3C7")
        (field (name "SOURCE") "Digikey")
      )
      (libsource (lib "ScoreBoard") (part "LRCOVLFR3C7Z"))
    )
    (comp (ref "DS150")
      (value "RED T1-3/4")
      (footprint "LED T1-3/4 Flush")
      (description "Optek LED Red /Clear High Brightness T1-3/4")
      (fields
        (field (name "MANUFACTURER") "TT Electronics/Optek Technology")
        (field (name "MANUFACTURER PART NUMBER") "OVLFR3C7")
        (field (name "SOURCE") "Digikey")
      )
      (libsource (lib "ScoreBoard") (part "LRCOVLFR3C7Z"))
    )
    (comp (ref "DS157")
      (value "RED T1-3/4")
      (footprint "LED T1-3/4 Flush")
      (description "Optek LED Red /Clear High Brightness T1-3/4")
      (fields
        (field (name "MANUFACTURER") "TT Electronics/Optek Technology")
        (field (name "MANUFACTURER PART NUMBER") "OVLFR3C7")
        (field (name "SOURCE") "Digikey")
      )
      (libsource (lib "ScoreBoard") (part "LRCOVLFR3C7Z"))
    )
    (comp (ref "DS158")
      (value "RED T1-3/4")
      (footprint "LED T1-3/4 Flush")
      (description "Optek LED Red /Clear High Brightness T1-3/4")
      (fields
        (field (name "MANUFACTURER") "TT Electronics/Optek Technology")
        (field (name "MANUFACTURER PART NUMBER") "OVLFR3C7")
        (field (name "SOURCE") "Digikey")
      )
      (libsource (lib "ScoreBoard") (part "LRCOVLFR3C7Z"))
    )
    (comp (ref "DS159")
      (value "RED T1-3/4")
      (footprint "LED T1-3/4 Flush")
      (description "Optek LED Red /Clear High Brightness T1-3/4")
      (fields
        (field (name "MANUFACTURER") "TT Electronics/Optek Technology")
        (field (name "MANUFACTURER PART NUMBER") "OVLFR3C7")
        (field (name "SOURCE") "Digikey")
      )
      (libsource (lib "ScoreBoard") (part "LRCOVLFR3C7Z"))
    )
    (comp (ref "DS160")
      (value "RED T1-3/4")
      (footprint "LED T1-3/4 Flush")
      (description "Optek LED Red /Clear High Brightness T1-3/4")
      (fields
        (field (name "MANUFACTURER") "TT Electronics/Optek Technology")
        (field (name "MANUFACTURER PART NUMBER") "OVLFR3C7")
        (field (name "SOURCE") "Digikey")
      )
      (libsource (lib "ScoreBoard") (part "LRCOVLFR3C7Z"))
    )
    (comp (ref "DS161")
      (value "RED T1-3/4")
      (footprint "LED T1-3/4 Flush")
      (description "Optek LED Red /Clear High Brightness T1-3/4")
      (fields
        (field (name "MANUFACTURER") "TT Electronics/Optek Technology")
        (field (name "MANUFACTURER PART NUMBER") "OVLFR3C7")
        (field (name "SOURCE") "Digikey")
      )
      (libsource (lib "ScoreBoard") (part "LRCOVLFR3C7Z"))
    )
    (comp (ref "DS162")
      (value "RED T1-3/4")
      (footprint "LED T1-3/4 Flush")
      (description "Optek LED Red /Clear High Brightness T1-3/4")
      (fields
        (field (name "MANUFACTURER") "TT Electronics/Optek Technology")
        (field (name "MANUFACTURER PART NUMBER") "OVLFR3C7")
        (field (name "SOURCE") "Digikey")
      )
      (libsource (lib "ScoreBoard") (part "LRCOVLFR3C7Z"))
    )
    (comp (ref "Q22")
      (value "BCX70K")
      (footprint "SOT23")
      (description "TRANS NPN AF 45V SOT-23")
      (fields (field (name "MANUFACTURER") "Fairchild Semiconductor") (field (name "SOURCE") "Digikey"))
      (libsource (lib "ScoreBoard") (part "QS/BCX70K00Z"))
    )
    (comp (ref "Q23")
      (value "BCX70K")
      (footprint "SOT23")
      (description "TRANS NPN AF 45V SOT-23")
      (fields (field (name "MANUFACTURER") "Fairchild Semiconductor") (field (name "SOURCE") "Digikey"))
      (libsource (lib "ScoreBoard") (part "QS/BCX70K00Z"))
    )
    (comp (ref "Q24")
      (value "BCX70K")
      (footprint "SOT23")
      (description "TRANS NPN AF 45V SOT-23")
      (fields (field (name "MANUFACTURER") "Fairchild Semiconductor") (field (name "SOURCE") "Digikey"))
      (libsource (lib "ScoreBoard") (part "QS/BCX70K00Z"))
    )
    (comp (ref "Q28")
      (value "BCX70K")
      (footprint "SOT23")
      (description "TRANS NPN AF 45V SOT-23")
      (fields (field (name "MANUFACTURER") "Fairchild Semiconductor") (field (name "SOURCE") "Digikey"))
      (libsource (lib "ScoreBoard") (part "QS/BCX70K00Z"))
    )
    (comp (ref "Q29")
      (value "BCX70K")
      (footprint "SOT23")
      (description "TRANS NPN AF 45V SOT-23")
      (fields (field (name "MANUFACTURER") "Fairchild Semiconductor") (field (name "SOURCE") "Digikey"))
      (libsource (lib "ScoreBoard") (part "QS/BCX70K00Z"))
    )
    (comp (ref "Q30")
      (value "BCX70K")
      (footprint "SOT23")
      (description "TRANS NPN AF 45V SOT-23")
      (fields (field (name "MANUFACTURER") "Fairchild Semiconductor") (field (name "SOURCE") "Digikey"))
      (libsource (lib "ScoreBoard") (part "QS/BCX70K00Z"))
    )
    (comp (ref "Q34")
      (value "BCX70K")
      (footprint "SOT23")
      (description "TRANS NPN AF 45V SOT-23")
      (fields (field (name "MANUFACTURER") "Fairchild Semiconductor") (field (name "SOURCE") "Digikey"))
      (libsource (lib "ScoreBoard") (part "QS/BCX70K00Z"))
    )
    (comp (ref "Q35")
      (value "BCX70K")
      (footprint "SOT23")
      (description "TRANS NPN AF 45V SOT-23")
      (fields (field (name "MANUFACTURER") "Fairchild Semiconductor") (field (name "SOURCE") "Digikey"))
      (libsource (lib "ScoreBoard") (part "QS/BCX70K00Z"))
    )
    (comp (ref "Q36")
      (value "BCX70K")
      (footprint "SOT23")
      (description "TRANS NPN AF 45V SOT-23")
      (fields (field (name "MANUFACTURER") "Fairchild Semiconductor") (field (name "SOURCE") "Digikey"))
      (libsource (lib "ScoreBoard") (part "QS/BCX70K00Z"))
    )
    (comp (ref "Q40")
      (value "BCX70K")
      (footprint "SOT23")
      (description "TRANS NPN AF 45V SOT-23")
      (fields (field (name "MANUFACTURER") "Fairchild Semiconductor") (field (name "SOURCE") "Digikey"))
      (libsource (lib "ScoreBoard") (part "QS/BCX70K00Z"))
    )
    (comp (ref "Q41")
      (value "BCX70K")
      (footprint "SOT23")
      (description "TRANS NPN AF 45V SOT-23")
      (fields (field (name "MANUFACTURER") "Fairchild Semiconductor") (field (name "SOURCE") "Digikey"))
      (libsource (lib "ScoreBoard") (part "QS/BCX70K00Z"))
    )
    (comp (ref "Q42")
      (value "BCX70K")
      (footprint "SOT23")
      (description "TRANS NPN AF 45V SOT-23")
      (fields (field (name "MANUFACTURER") "Fairchild Semiconductor") (field (name "SOURCE") "Digikey"))
      (libsource (lib "ScoreBoard") (part "QS/BCX70K00Z"))
    )
    (comp (ref "Q46")
      (value "BCX70K")
      (footprint "SOT23")
      (description "TRANS NPN AF 45V SOT-23")
      (fields (field (name "MANUFACTURER") "Fairchild Semiconductor") (field (name "SOURCE") "Digikey"))
      (libsource (lib "ScoreBoard") (part "QS/BCX70K00Z"))
    )
    (comp (ref "Q47")
      (value "BCX70K")
      (footprint "SOT23")
      (description "TRANS NPN AF 45V SOT-23")
      (fields (field (name "MANUFACTURER") "Fairchild Semiconductor") (field (name "SOURCE") "Digikey"))
      (libsource (lib "ScoreBoard") (part "QS/BCX70K00Z"))
    )
    (comp (ref "Q48")
      (value "BCX70K")
      (footprint "SOT23")
      (description "TRANS NPN AF 45V SOT-23")
      (fields (field (name "MANUFACTURER") "Fairchild Semiconductor") (field (name "SOURCE") "Digikey"))
      (libsource (lib "ScoreBoard") (part "QS/BCX70K00Z"))
    )
    (comp (ref "Q52")
      (value "BCX70K")
      (footprint "SOT23")
      (description "TRANS NPN AF 45V SOT-23")
      (fields (field (name "MANUFACTURER") "Fairchild Semiconductor") (field (name "SOURCE") "Digikey"))
      (libsource (lib "ScoreBoard") (part "QS/BCX70K00Z"))
    )
    (comp (ref "Q53")
      (value "BCX70K")
      (footprint "SOT23")
      (description "TRANS NPN AF 45V SOT-23")
      (fields (field (name "MANUFACTURER") "Fairchild Semiconductor") (field (name "SOURCE") "Digikey"))
      (libsource (lib "ScoreBoard") (part "QS/BCX70K00Z"))
    )
    (comp (ref "Q54")
      (value "BCX70K")
      (footprint "SOT23")
      (description "TRANS NPN AF 45V SOT-23")
      (fields (field (name "MANUFACTURER") "Fairchild Semiconductor") (field (name "SOURCE") "Digikey"))
      (libsource (lib "ScoreBoard") (part "QS/BCX70K00Z"))
    )
    (comp (ref "Q58")
      (value "BCX70K")
      (footprint "SOT23")
      (description "TRANS NPN AF 45V SOT-23")
      (fields (field (name "MANUFACTURER") "Fairchild Semiconductor") (field (name "SOURCE") "Digikey"))
      (libsource (lib "ScoreBoard") (part "QS/BCX70K00Z"))
    )
    (comp (ref "Q59")
      (value "BCX70K")
      (footprint "SOT23")
      (description "TRANS NPN AF 45V SOT-23")
      (fields (field (name "MANUFACTURER") "Fairchild Semiconductor") (field (name "SOURCE") "Digikey"))
      (libsource (lib "ScoreBoard") (part "QS/BCX70K00Z"))
    )
    (comp (ref "Q60")
      (value "BCX70K")
      (footprint "SOT23")
      (description "TRANS NPN AF 45V SOT-23")
      (fields (field (name "MANUFACTURER") "Fairchild Semiconductor") (field (name "SOURCE") "Digikey"))
      (libsource (lib "ScoreBoard") (part "QS/BCX70K00Z"))
    )
    (comp (ref "R105")
      (value "5.1k")
      (footprint "R0805")
      (description "RES 5.10K OHM 1/8W 1% 0805 SMD")
      (fields
        (field (name "MANUFACTURER") "Panasonic - ECG")
        (field (name "MANUFACTURER PART NUMBER") "ERJ-6ENF5101V")
      )
      (libsource (lib "eRCL") (part "ERJ-6ENF5101V"))
    )
    (comp (ref "R106")
      (value "5.1k")
      (footprint "R0805")
      (description "RES 5.10K OHM 1/8W 1% 0805 SMD")
      (fields
        (field (name "MANUFACTURER") "Panasonic - ECG")
        (field (name "MANUFACTURER PART NUMBER") "ERJ-6ENF5101V")
      )
      (libsource (lib "eRCL") (part "ERJ-6ENF5101V"))
    )
    (comp (ref "R107")
      (value "5.1k")
      (footprint "R0805")
      (description "RES 5.10K OHM 1/8W 1% 0805 SMD")
      (fields
        (field (name "MANUFACTURER") "Panasonic - ECG")
        (field (name "MANUFACTURER PART NUMBER") "ERJ-6ENF5101V")
      )
      (libsource (lib "eRCL") (part "ERJ-6ENF5101V"))
    )
    (comp (ref "R111")
      (value "180")
      (footprint "R1206")
      (description "RES 180 OHM 1/4W 1% 1206 SMD")
      (fields
        (field (name "MANUFACTURER") "Panasonic - ECG")
        (field (name "MANUFACTURER PART NUMBER") "ERJ-8ENF1800V")
      )
      (libsource (lib "eRCL") (part "ERJ-8ENF1800V"))
    )
    (comp (ref "R112")
      (value "180")
      (footprint "R1206")
      (description "RES 180 OHM 1/4W 1% 1206 SMD")
      (fields
        (field (name "MANUFACTURER") "Panasonic - ECG")
        (field (name "MANUFACTURER PART NUMBER") "ERJ-8ENF1800V")
      )
      (libsource (lib "eRCL") (part "ERJ-8ENF1800V"))
    )
    (comp (ref "R113")
      (value "180")
      (footprint "R1206")
      (description "RES 180 OHM 1/4W 1% 1206 SMD")
      (fields
        (field (name "MANUFACTURER") "Panasonic - ECG")
        (field (name "MANUFACTURER PART NUMBER") "ERJ-8ENF1800V")
      )
      (libsource (lib "eRCL") (part "ERJ-8ENF1800V"))
    )
    (comp (ref "R117")
      (value "180")
      (footprint "R1206")
      (description "RES 180 OHM 1/4W 1% 1206 SMD")
      (fields
        (field (name "MANUFACTURER") "Panasonic - ECG")
        (field (name "MANUFACTURER PART NUMBER") "ERJ-8ENF1800V")
      )
      (libsource (lib "eRCL") (part "ERJ-8ENF1800V"))
    )
    (comp (ref "R118")
      (value "180")
      (footprint "R1206")
      (description "RES 180 OHM 1/4W 1% 1206 SMD")
      (fields
        (field (name "MANUFACTURER") "Panasonic - ECG")
        (field (name "MANUFACTURER PART NUMBER") "ERJ-8ENF1800V")
      )
      (libsource (lib "eRCL") (part "ERJ-8ENF1800V"))
    )
    (comp (ref "R119")
      (value "180")
      (footprint "R1206")
      (description "RES 180 OHM 1/4W 1% 1206 SMD")
      (fields
        (field (name "MANUFACTURER") "Panasonic - ECG")
        (field (name "MANUFACTURER PART NUMBER") "ERJ-8ENF1800V")
      )
      (libsource (lib "eRCL") (part "ERJ-8ENF1800V"))
    )
    (comp (ref "R123")
      (value "5.1k")
      (footprint "R0805")
      (description "RES 5.10K OHM 1/8W 1% 0805 SMD")
      (fields
        (field (name "MANUFACTURER") "Panasonic - ECG")
        (field (name "MANUFACTURER PART NUMBER") "ERJ-6ENF5101V")
      )
      (libsource (lib "eRCL") (part "ERJ-6ENF5101V"))
    )
    (comp (ref "R124")
      (value "5.1k")
      (footprint "R0805")
      (description "RES 5.10K OHM 1/8W 1% 0805 SMD")
      (fields
        (field (name "MANUFACTURER") "Panasonic - ECG")
        (field (name "MANUFACTURER PART NUMBER") "ERJ-6ENF5101V")
      )
      (libsource (lib "eRCL") (part "ERJ-6ENF5101V"))
    )
    (comp (ref "R125")
      (value "5.1k")
      (footprint "R0805")
      (description "RES 5.10K OHM 1/8W 1% 0805 SMD")
      (fields
        (field (name "MANUFACTURER") "Panasonic - ECG")
        (field (name "MANUFACTURER PART NUMBER") "ERJ-6ENF5101V")
      )
      (libsource (lib "eRCL") (part "ERJ-6ENF5101V"))
    )
    (comp (ref "R129")
      (value "180")
      (footprint "R1206")
      (description "RES 180 OHM 1/4W 1% 1206 SMD")
      (fields
        (field (name "MANUFACTURER") "Panasonic - ECG")
        (field (name "MANUFACTURER PART NUMBER") "ERJ-8ENF1800V")
      )
      (libsource (lib "eRCL") (part "ERJ-8ENF1800V"))
    )
    (comp (ref "R130")
      (value "180")
      (footprint "R1206")
      (description "RES 180 OHM 1/4W 1% 1206 SMD")
      (fields
        (field (name "MANUFACTURER") "Panasonic - ECG")
        (field (name "MANUFACTURER PART NUMBER") "ERJ-8ENF1800V")
      )
      (libsource (lib "eRCL") (part "ERJ-8ENF1800V"))
    )
    (comp (ref "R131")
      (value "180")
      (footprint "R1206")
      (description "RES 180 OHM 1/4W 1% 1206 SMD")
      (fields
        (field (name "MANUFACTURER") "Panasonic - ECG")
        (field (name "MANUFACTURER PART NUMBER") "ERJ-8ENF1800V")
      )
      (libsource (lib "eRCL") (part "ERJ-8ENF1800V"))
    )
    (comp (ref "R135")
      (value "180")
      (footprint "R1206")
      (description "RES 180 OHM 1/4W 1% 1206 SMD")
      (fields
        (field (name "MANUFACTURER") "Panasonic - ECG")
        (field (name "MANUFACTURER PART NUMBER") "ERJ-8ENF1800V")
      )
      (libsource (lib "eRCL") (part "ERJ-8ENF1800V"))
    )
    (comp (ref "R136")
      (value "180")
      (footprint "R1206")
      (description "RES 180 OHM 1/4W 1% 1206 SMD")
      (fields
        (field (name "MANUFACTURER") "Panasonic - ECG")
        (field (name "MANUFACTURER PART NUMBER") "ERJ-8ENF1800V")
      )
      (libsource (lib "eRCL") (part "ERJ-8ENF1800V"))
    )
    (comp (ref "R137")
      (value "180")
      (footprint "R1206")
      (description "RES 180 OHM 1/4W 1% 1206 SMD")
      (fields
        (field (name "MANUFACTURER") "Panasonic - ECG")
        (field (name "MANUFACTURER PART NUMBER") "ERJ-8ENF1800V")
      )
      (libsource (lib "eRCL") (part "ERJ-8ENF1800V"))
    )
    (comp (ref "R141")
      (value "5.1k")
      (footprint "R0805")
      (description "RES 5.10K OHM 1/8W 1% 0805 SMD")
      (fields
        (field (name "MANUFACTURER") "Panasonic - ECG")
        (field (name "MANUFACTURER PART NUMBER") "ERJ-6ENF5101V")
      )
      (libsource (lib "eRCL") (part "ERJ-6ENF5101V"))
    )
    (comp (ref "R142")
      (value "5.1k")
      (footprint "R0805")
      (description "RES 5.10K OHM 1/8W 1% 0805 SMD")
      (fields
        (field (name "MANUFACTURER") "Panasonic - ECG")
        (field (name "MANUFACTURER PART NUMBER") "ERJ-6ENF5101V")
      )
      (libsource (lib "eRCL") (part "ERJ-6ENF5101V"))
    )
    (comp (ref "R143")
      (value "5.1k")
      (footprint "R0805")
      (description "RES 5.10K OHM 1/8W 1% 0805 SMD")
      (fields
        (field (name "MANUFACTURER") "Panasonic - ECG")
        (field (name "MANUFACTURER PART NUMBER") "ERJ-6ENF5101V")
      )
      (libsource (lib "eRCL") (part "ERJ-6ENF5101V"))
    )
    (comp (ref "R147")
      (value "180")
      (footprint "R1206")
      (description "RES 180 OHM 1/4W 1% 1206 SMD")
      (fields
        (field (name "MANUFACTURER") "Panasonic - ECG")
        (field (name "MANUFACTURER PART NUMBER") "ERJ-8ENF1800V")
      )
      (libsource (lib "eRCL") (part "ERJ-8ENF1800V"))
    )
    (comp (ref "R148")
      (value "180")
      (footprint "R1206")
      (description "RES 180 OHM 1/4W 1% 1206 SMD")
      (fields
        (field (name "MANUFACTURER") "Panasonic - ECG")
        (field (name "MANUFACTURER PART NUMBER") "ERJ-8ENF1800V")
      )
      (libsource (lib "eRCL") (part "ERJ-8ENF1800V"))
    )
    (comp (ref "R149")
      (value "180")
      (footprint "R1206")
      (description "RES 180 OHM 1/4W 1% 1206 SMD")
      (fields
        (field (name "MANUFACTURER") "Panasonic - ECG")
        (field (name "MANUFACTURER PART NUMBER") "ERJ-8ENF1800V")
      )
      (libsource (lib "eRCL") (part "ERJ-8ENF1800V"))
    )
    (comp (ref "R153")
      (value "180")
      (footprint "R1206")
      (description "RES 180 OHM 1/4W 1% 1206 SMD")
      (fields
        (field (name "MANUFACTURER") "Panasonic - ECG")
        (field (name "MANUFACTURER PART NUMBER") "ERJ-8ENF1800V")
      )
      (libsource (lib "eRCL") (part "ERJ-8ENF1800V"))
    )
    (comp (ref "R154")
      (value "180")
      (footprint "R1206")
      (description "RES 180 OHM 1/4W 1% 1206 SMD")
      (fields
        (field (name "MANUFACTURER") "Panasonic - ECG")
        (field (name "MANUFACTURER PART NUMBER") "ERJ-8ENF1800V")
      )
      (libsource (lib "eRCL") (part "ERJ-8ENF1800V"))
    )
    (comp (ref "R155")
      (value "180")
      (footprint "R1206")
      (description "RES 180 OHM 1/4W 1% 1206 SMD")
      (fields
        (field (name "MANUFACTURER") "Panasonic - ECG")
        (field (name "MANUFACTURER PART NUMBER") "ERJ-8ENF1800V")
      )
      (libsource (lib "eRCL") (part "ERJ-8ENF1800V"))
    )
    (comp (ref "R159")
      (value "5.1k")
      (footprint "R0805")
      (description "RES 5.10K OHM 1/8W 1% 0805 SMD")
      (fields
        (field (name "MANUFACTURER") "Panasonic - ECG")
        (field (name "MANUFACTURER PART NUMBER") "ERJ-6ENF5101V")
      )
      (libsource (lib "eRCL") (part "ERJ-6ENF5101V"))
    )
    (comp (ref "R160")
      (value "5.1k")
      (footprint "R0805")
      (description "RES 5.10K OHM 1/8W 1% 0805 SMD")
      (fields
        (field (name "MANUFACTURER") "Panasonic - ECG")
        (field (name "MANUFACTURER PART NUMBER") "ERJ-6ENF5101V")
      )
      (libsource (lib "eRCL") (part "ERJ-6ENF5101V"))
    )
    (comp (ref "R161")
      (value "5.1k")
      (footprint "R0805")
      (description "RES 5.10K OHM 1/8W 1% 0805 SMD")
      (fields
        (field (name "MANUFACTURER") "Panasonic - ECG")
        (field (name "MANUFACTURER PART NUMBER") "ERJ-6ENF5101V")
      )
      (libsource (lib "eRCL") (part "ERJ-6ENF5101V"))
    )
    (comp (ref "R165")
      (value "180")
      (footprint "R1206")
      (description "RES 180 OHM 1/4W 1% 1206 SMD")
      (fields
        (field (name "MANUFACTURER") "Panasonic - ECG")
        (field (name "MANUFACTURER PART NUMBER") "ERJ-8ENF1800V")
      )
      (libsource (lib "eRCL") (part "ERJ-8ENF1800V"))
    )
    (comp (ref "R166")
      (value "180")
      (footprint "R1206")
      (description "RES 180 OHM 1/4W 1% 1206 SMD")
      (fields
        (field (name "MANUFACTURER") "Panasonic - ECG")
        (field (name "MANUFACTURER PART NUMBER") "ERJ-8ENF1800V")
      )
      (libsource (lib "eRCL") (part "ERJ-8ENF1800V"))
    )
    (comp (ref "R167")
      (value "180")
      (footprint "R1206")
      (description "RES 180 OHM 1/4W 1% 1206 SMD")
      (fields
        (field (name "MANUFACTURER") "Panasonic - ECG")
        (field (name "MANUFACTURER PART NUMBER") "ERJ-8ENF1800V")
      )
      (libsource (lib "eRCL") (part "ERJ-8ENF1800V"))
    )
    (comp (ref "R171")
      (value "180")
      (footprint "R1206")
      (description "RES 180 OHM 1/4W 1% 1206 SMD")
      (fields
        (field (name "MANUFACTURER") "Panasonic - ECG")
        (field (name "MANUFACTURER PART NUMBER") "ERJ-8ENF1800V")
      )
      (libsource (lib "eRCL") (part "ERJ-8ENF1800V"))
    )
    (comp (ref "R172")
      (value "180")
      (footprint "R1206")
      (description "RES 180 OHM 1/4W 1% 1206 SMD")
      (fields
        (field (name "MANUFACTURER") "Panasonic - ECG")
        (field (name "MANUFACTURER PART NUMBER") "ERJ-8ENF1800V")
      )
      (libsource (lib "eRCL") (part "ERJ-8ENF1800V"))
    )
    (comp (ref "R173")
      (value "180")
      (footprint "R1206")
      (description "RES 180 OHM 1/4W 1% 1206 SMD")
      (fields
        (field (name "MANUFACTURER") "Panasonic - ECG")
        (field (name "MANUFACTURER PART NUMBER") "ERJ-8ENF1800V")
      )
      (libsource (lib "eRCL") (part "ERJ-8ENF1800V"))
    )
    (comp (ref "R177")
      (value "5.1k")
      (footprint "R0805")
      (description "RES 5.10K OHM 1/8W 1% 0805 SMD")
      (fields
        (field (name "MANUFACTURER") "Panasonic - ECG")
        (field (name "MANUFACTURER PART NUMBER") "ERJ-6ENF5101V")
      )
      (libsource (lib "eRCL") (part "ERJ-6ENF5101V"))
    )
    (comp (ref "R178")
      (value "5.1k")
      (footprint "R0805")
      (description "RES 5.10K OHM 1/8W 1% 0805 SMD")
      (fields
        (field (name "MANUFACTURER") "Panasonic - ECG")
        (field (name "MANUFACTURER PART NUMBER") "ERJ-6ENF5101V")
      )
      (libsource (lib "eRCL") (part "ERJ-6ENF5101V"))
    )
    (comp (ref "R179")
      (value "5.1k")
      (footprint "R0805")
      (description "RES 5.10K OHM 1/8W 1% 0805 SMD")
      (fields
        (field (name "MANUFACTURER") "Panasonic - ECG")
        (field (name "MANUFACTURER PART NUMBER") "ERJ-6ENF5101V")
      )
      (libsource (lib "eRCL") (part "ERJ-6ENF5101V"))
    )
    (comp (ref "R183")
      (value "180")
      (footprint "R1206")
      (description "RES 180 OHM 1/4W 1% 1206 SMD")
      (fields
        (field (name "MANUFACTURER") "Panasonic - ECG")
        (field (name "MANUFACTURER PART NUMBER") "ERJ-8ENF1800V")
      )
      (libsource (lib "eRCL") (part "ERJ-8ENF1800V"))
    )
    (comp (ref "R184")
      (value "180")
      (footprint "R1206")
      (description "RES 180 OHM 1/4W 1% 1206 SMD")
      (fields
        (field (name "MANUFACTURER") "Panasonic - ECG")
        (field (name "MANUFACTURER PART NUMBER") "ERJ-8ENF1800V")
      )
      (libsource (lib "eRCL") (part "ERJ-8ENF1800V"))
    )
    (comp (ref "R185")
      (value "180")
      (footprint "R1206")
      (description "RES 180 OHM 1/4W 1% 1206 SMD")
      (fields
        (field (name "MANUFACTURER") "Panasonic - ECG")
        (field (name "MANUFACTURER PART NUMBER") "ERJ-8ENF1800V")
      )
      (libsource (lib "eRCL") (part "ERJ-8ENF1800V"))
    )
    (comp (ref "R189")
      (value "180")
      (footprint "R1206")
      (description "RES 180 OHM 1/4W 1% 1206 SMD")
      (fields
        (field (name "MANUFACTURER") "Panasonic - ECG")
        (field (name "MANUFACTURER PART NUMBER") "ERJ-8ENF1800V")
      )
      (libsource (lib "eRCL") (part "ERJ-8ENF1800V"))
    )
    (comp (ref "R190")
      (value "180")
      (footprint "R1206")
      (description "RES 180 OHM 1/4W 1% 1206 SMD")
      (fields
        (field (name "MANUFACTURER") "Panasonic - ECG")
        (field (name "MANUFACTURER PART NUMBER") "ERJ-8ENF1800V")
      )
      (libsource (lib "eRCL") (part "ERJ-8ENF1800V"))
    )
    (comp (ref "R191")
      (value "180")
      (footprint "R1206")
      (description "RES 180 OHM 1/4W 1% 1206 SMD")
      (fields
        (field (name "MANUFACTURER") "Panasonic - ECG")
        (field (name "MANUFACTURER PART NUMBER") "ERJ-8ENF1800V")
      )
      (libsource (lib "eRCL") (part "ERJ-8ENF1800V"))
    )
    (comp (ref "R195")
      (value "5.1k")
      (footprint "R0805")
      (description "RES 5.10K OHM 1/8W 1% 0805 SMD")
      (fields
        (field (name "MANUFACTURER") "Panasonic - ECG")
        (field (name "MANUFACTURER PART NUMBER") "ERJ-6ENF5101V")
      )
      (libsource (lib "eRCL") (part "ERJ-6ENF5101V"))
    )
    (comp (ref "R196")
      (value "5.1k")
      (footprint "R0805")
      (description "RES 5.10K OHM 1/8W 1% 0805 SMD")
      (fields
        (field (name "MANUFACTURER") "Panasonic - ECG")
        (field (name "MANUFACTURER PART NUMBER") "ERJ-6ENF5101V")
      )
      (libsource (lib "eRCL") (part "ERJ-6ENF5101V"))
    )
    (comp (ref "R197")
      (value "5.1k")
      (footprint "R0805")
      (description "RES 5.10K OHM 1/8W 1% 0805 SMD")
      (fields
        (field (name "MANUFACTURER") "Panasonic - ECG")
        (field (name "MANUFACTURER PART NUMBER") "ERJ-6ENF5101V")
      )
      (libsource (lib "eRCL") (part "ERJ-6ENF5101V"))
    )
    (comp (ref "R201")
      (value "180")
      (footprint "R1206")
      (description "RES 180 OHM 1/4W 1% 1206 SMD")
      (fields
        (field (name "MANUFACTURER") "Panasonic - ECG")
        (field (name "MANUFACTURER PART NUMBER") "ERJ-8ENF1800V")
      )
      (libsource (lib "eRCL") (part "ERJ-8ENF1800V"))
    )
    (comp (ref "R202")
      (value "180")
      (footprint "R1206")
      (description "RES 180 OHM 1/4W 1% 1206 SMD")
      (fields
        (field (name "MANUFACTURER") "Panasonic - ECG")
        (field (name "MANUFACTURER PART NUMBER") "ERJ-8ENF1800V")
      )
      (libsource (lib "eRCL") (part "ERJ-8ENF1800V"))
    )
    (comp (ref "R203")
      (value "180")
      (footprint "R1206")
      (description "RES 180 OHM 1/4W 1% 1206 SMD")
      (fields
        (field (name "MANUFACTURER") "Panasonic - ECG")
        (field (name "MANUFACTURER PART NUMBER") "ERJ-8ENF1800V")
      )
      (libsource (lib "eRCL") (part "ERJ-8ENF1800V"))
    )
    (comp (ref "R207")
      (value "180")
      (footprint "R1206")
      (description "RES 180 OHM 1/4W 1% 1206 SMD")
      (fields
        (field (name "MANUFACTURER") "Panasonic - ECG")
        (field (name "MANUFACTURER PART NUMBER") "ERJ-8ENF1800V")
      )
      (libsource (lib "eRCL") (part "ERJ-8ENF1800V"))
    )
    (comp (ref "R208")
      (value "180")
      (footprint "R1206")
      (description "RES 180 OHM 1/4W 1% 1206 SMD")
      (fields
        (field (name "MANUFACTURER") "Panasonic - ECG")
        (field (name "MANUFACTURER PART NUMBER") "ERJ-8ENF1800V")
      )
      (libsource (lib "eRCL") (part "ERJ-8ENF1800V"))
    )
    (comp (ref "R209")
      (value "180")
      (footprint "R1206")
      (description "RES 180 OHM 1/4W 1% 1206 SMD")
      (fields
        (field (name "MANUFACTURER") "Panasonic - ECG")
        (field (name "MANUFACTURER PART NUMBER") "ERJ-8ENF1800V")
      )
      (libsource (lib "eRCL") (part "ERJ-8ENF1800V"))
    )
    (comp (ref "R213")
      (value "5.1k")
      (footprint "R0805")
      (description "RES 5.10K OHM 1/8W 1% 0805 SMD")
      (fields
        (field (name "MANUFACTURER") "Panasonic - ECG")
        (field (name "MANUFACTURER PART NUMBER") "ERJ-6ENF5101V")
      )
      (libsource (lib "eRCL") (part "ERJ-6ENF5101V"))
    )
    (comp (ref "R214")
      (value "5.1k")
      (footprint "R0805")
      (description "RES 5.10K OHM 1/8W 1% 0805 SMD")
      (fields
        (field (name "MANUFACTURER") "Panasonic - ECG")
        (field (name "MANUFACTURER PART NUMBER") "ERJ-6ENF5101V")
      )
      (libsource (lib "eRCL") (part "ERJ-6ENF5101V"))
    )
    (comp (ref "R215")
      (value "5.1k")
      (footprint "R0805")
      (description "RES 5.10K OHM 1/8W 1% 0805 SMD")
      (fields
        (field (name "MANUFACTURER") "Panasonic - ECG")
        (field (name "MANUFACTURER PART NUMBER") "ERJ-6ENF5101V")
      )
      (libsource (lib "eRCL") (part "ERJ-6ENF5101V"))
    )
    (comp (ref "R219")
      (value "180")
      (footprint "R1206")
      (description "RES 180 OHM 1/4W 1% 1206 SMD")
      (fields
        (field (name "MANUFACTURER") "Panasonic - ECG")
        (field (name "MANUFACTURER PART NUMBER") "ERJ-8ENF1800V")
      )
      (libsource (lib "eRCL") (part "ERJ-8ENF1800V"))
    )
    (comp (ref "R220")
      (value "180")
      (footprint "R1206")
      (description "RES 180 OHM 1/4W 1% 1206 SMD")
      (fields
        (field (name "MANUFACTURER") "Panasonic - ECG")
        (field (name "MANUFACTURER PART NUMBER") "ERJ-8ENF1800V")
      )
      (libsource (lib "eRCL") (part "ERJ-8ENF1800V"))
    )
    (comp (ref "R221")
      (value "180")
      (footprint "R1206")
      (description "RES 180 OHM 1/4W 1% 1206 SMD")
      (fields
        (field (name "MANUFACTURER") "Panasonic - ECG")
        (field (name "MANUFACTURER PART NUMBER") "ERJ-8ENF1800V")
      )
      (libsource (lib "eRCL") (part "ERJ-8ENF1800V"))
    )
    (comp (ref "R225")
      (value "180")
      (footprint "R1206")
      (description "RES 180 OHM 1/4W 1% 1206 SMD")
      (fields
        (field (name "MANUFACTURER") "Panasonic - ECG")
        (field (name "MANUFACTURER PART NUMBER") "ERJ-8ENF1800V")
      )
      (libsource (lib "eRCL") (part "ERJ-8ENF1800V"))
    )
    (comp (ref "R226")
      (value "180")
      (footprint "R1206")
      (description "RES 180 OHM 1/4W 1% 1206 SMD")
      (fields
        (field (name "MANUFACTURER") "Panasonic - ECG")
        (field (name "MANUFACTURER PART NUMBER") "ERJ-8ENF1800V")
      )
      (libsource (lib "eRCL") (part "ERJ-8ENF1800V"))
    )
    (comp (ref "R227")
      (value "180")
      (footprint "R1206")
      (description "RES 180 OHM 1/4W 1% 1206 SMD")
      (fields
        (field (name "MANUFACTURER") "Panasonic - ECG")
        (field (name "MANUFACTURER PART NUMBER") "ERJ-8ENF1800V")
      )
      (libsource (lib "eRCL") (part "ERJ-8ENF1800V"))
    )
    (comp (ref "U19")
      (value "IS/SN74HC573DWZ")
      (footprint "SOIC300-20")
      (description "Octal D-Type Transparent Latch with 3-State Outputs")
      (fields
        (field (name "MANUFACTURER") "NXP Semiconductors")
        (field (name "MANUFACTURER PART NUMBER") "74HC573D-T")
        (field (name "SOURCE") "Digikey")
      )
      (libsource (lib "ScoreBoard") (part "IS/SN74HC573DWZ"))
    )
    (comp (ref "U20")
      (value "IS/SN74HC573DWZ")
      (footprint "SOIC300-20")
      (description "Octal D-Type Transparent Latch with 3-State Outputs")
      (fields
        (field (name "MANUFACTURER") "NXP Semiconductors")
        (field (name "MANUFACTURER PART NUMBER") "74HC573D-T")
        (field (name "SOURCE") "Digikey")
      )
      (libsource (lib "ScoreBoard") (part "IS/SN74HC573DWZ"))
    )
    (comp (ref "U21")
      (value "IS/SN74HC573DWZ")
      (footprint "SOIC300-20")
      (description "Octal D-Type Transparent Latch with 3-State Outputs")
      (fields
        (field (name "MANUFACTURER") "NXP Semiconductors")
        (field (name "MANUFACTURER PART NUMBER") "74HC573D-T")
        (field (name "SOURCE") "Digikey")
      )
      (libsource (lib "ScoreBoard") (part "IS/SN74HC573DWZ"))
    )
  )
  (nets
    (net (code "1") (name "/8V") (class "Default")
      (node (ref "DS1") (pin "1") (pinfunction "A_1") (pintype "passive"))
      (node (ref "DS101") (pin "1") (pinfunction "A_1") (pintype "passive"))
      (node (ref "DS109") (pin "1") (pinfunction "A_1") (pintype "passive"))
      (node (ref "DS111") (pin "1") (pinfunction "A_1") (pintype "passive"))
      (node (ref "DS113") (pin "1") (pinfunction "A_1") (pintype "passive"))
      (node (ref "DS121") (pin "1") (pinfunction "A_1") (pintype "passive"))
      (node (ref "DS123") (pin "1") (pinfunction "A_1") (pintype "passive"))
      (node (ref "DS125") (pin "1") (pinfunction "A_1") (pintype "passive"))
      (node (ref "DS13") (pin "1") (pinfunction "A_1") (pintype "passive"))
      (node (ref "DS133") (pin "1") (pinfunction "A_1") (pintype "passive"))
      (node (ref "DS135") (pin "1") (pinfunction "A_1") (pintype "passive"))
      (node (ref "DS137") (pin "1") (pinfunction "A_1") (pintype "passive"))
      (node (ref "DS145") (pin "1") (pinfunction "A_1") (pintype "passive"))
      (node (ref "DS147") (pin "1") (pinfunction "A_1") (pintype "passive"))
      (node (ref "DS149") (pin "1") (pinfunction "A_1") (pintype "passive"))
      (node (ref "DS15") (pin "1") (pinfunction "A_1") (pintype "passive"))
      (node (ref "DS157") (pin "1") (pinfunction "A_1") (pintype "passive"))
      (node (ref "DS159") (pin "1") (pinfunction "A_1") (pintype "passive"))
      (node (ref "DS161") (pin "1") (pinfunction "A_1") (pintype "passive"))
      (node (ref "DS17") (pin "1") (pinfunction "A_1") (pintype "passive"))
      (node (ref "DS25") (pin "1") (pinfunction "A_1") (pintype "passive"))
      (node (ref "DS27") (pin "1") (pinfunction "A_1") (pintype "passive"))
      (node (ref "DS29") (pin "1") (pinfunction "A_1") (pintype "passive"))
      (node (ref "DS3") (pin "1") (pinfunction "A_1") (pintype "passive"))
      (node (ref "DS37") (pin "1") (pinfunction "A_1") (pintype "passive"))
      (node (ref "DS39") (pin "1") (pinfunction "A_1") (pintype "passive"))
      (node (ref "DS41") (pin "1") (pinfunction "A_1") (pintype "passive"))
      (node (ref "DS49") (pin "1") (pinfunction "A_1") (pintype "passive"))
      (node (ref "DS5") (pin "1") (pinfunction "A_1") (pintype "passive"))
      (node (ref "DS51") (pin "1") (pinfunction "A_1") (pintype "passive"))
      (node (ref "DS53") (pin "1") (pinfunction "A_1") (pintype "passive"))
      (node (ref "DS61") (pin "1") (pinfunction "A_1") (pintype "passive"))
      (node (ref "DS63") (pin "1") (pinfunction "A_1") (pintype "passive"))
      (node (ref "DS65") (pin "1") (pinfunction "A_1") (pintype "passive"))
      (node (ref "DS73") (pin "1") (pinfunction "A_1") (pintype "passive"))
      (node (ref "DS75") (pin "1") (pinfunction "A_1") (pintype "passive"))
      (node (ref "DS77") (pin "1") (pinfunction "A_1") (pintype "passive"))
      (node (ref "DS85") (pin "1") (pinfunction "A_1") (pintype "passive"))
      (node (ref "DS87") (pin "1") (pinfunction "A_1") (pintype "passive"))
      (node (ref "DS89") (pin "1") (pinfunction "A_1") (pintype "passive"))
      (node (ref "DS97") (pin "1") (pinfunction "A_1") (pintype "passive"))
      (node (ref "DS99") (pin "1") (pinfunction "A_1") (pintype "passive"))
    )
    (net (code "2") (name "/CLK0") (class "Default")
      (node (ref "U19") (pin "11") (pinfunction "LE_11") (pintype "input"))
    )
    (net (code "3") (name "/CLK1") (class "Default")
      (node (ref "U20") (pin "11") (pinfunction "LE_11") (pintype "input"))
    )
    (net (code "4") (name "/CLK2") (class "Default")
      (node (ref "U21") (pin "11") (pinfunction "LE_11") (pintype "input"))
    )
    (net (code "5") (name "/D0") (class "Default")
      (node (ref "U19") (pin "2") (pinfunction "D1_2") (pintype "input"))
      (node (ref "U20") (pin "2") (pinfunction "D1_2") (pintype "input"))
      (node (ref "U21") (pin "2") (pinfunction "D1_2") (pintype "input"))
    )
    (net (code "6") (name "/D1") (class "Default")
      (node (ref "U19") (pin "3") (pinfunction "D2_3") (pintype "input"))
      (node (ref "U20") (pin "3") (pinfunction "D2_3") (pintype "input"))
      (node (ref "U21") (pin "3") (pinfunction "D2_3") (pintype "input"))
    )
    (net (code "7") (name "/D2") (class "Default")
      (node (ref "U19") (pin "4") (pinfunction "D3_4") (pintype "input"))
      (node (ref "U20") (pin "4") (pinfunction "D3_4") (pintype "input"))
      (node (ref "U21") (pin "4") (pinfunction "D3_4") (pintype "input"))
    )
    (net (code "8") (name "/D3") (class "Default")
      (node (ref "U19") (pin "5") (pinfunction "D4_5") (pintype "input"))
      (node (ref "U20") (pin "5") (pinfunction "D4_5") (pintype "input"))
      (node (ref "U21") (pin "5") (pinfunction "D4_5") (pintype "input"))
    )
    (net (code "9") (name "/D4") (class "Default")
      (node (ref "U19") (pin "6") (pinfunction "D5_6") (pintype "input"))
      (node (ref "U20") (pin "6") (pinfunction "D5_6") (pintype "input"))
      (node (ref "U21") (pin "6") (pinfunction "D5_6") (pintype "input"))
    )
    (net (code "10") (name "/D5") (class "Default")
      (node (ref "U19") (pin "7") (pinfunction "D6_7") (pintype "input"))
      (node (ref "U20") (pin "7") (pinfunction "D6_7") (pintype "input"))
      (node (ref "U21") (pin "7") (pinfunction "D6_7") (pintype "input"))
    )
    (net (code "11") (name "/D6") (class "Default")
      (node (ref "U19") (pin "8") (pinfunction "D7_8") (pintype "input"))
      (node (ref "U20") (pin "8") (pinfunction "D7_8") (pintype "input"))
      (node (ref "U21") (pin "8") (pinfunction "D7_8") (pintype "input"))
    )
    (net (code "12") (name "/D7") (class "Default")
      (node (ref "U19") (pin "9") (pinfunction "D8_9") (pintype "input"))
      (node (ref "U20") (pin "9") (pinfunction "D8_9") (pintype "input"))
      (node (ref "U21") (pin "9") (pinfunction "D8_9") (pintype "input"))
    )
    (net (code "13") (name "/LAMP0") (class "Default")
      (node (ref "U19") (pin "12") (pinfunction "Q8_12") (pintype "tri_state"))
    )
    (net (code "14") (name "/LAMP1") (class "Default")
      (node (ref "U20") (pin "12") (pinfunction "Q8_12") (pintype "tri_state"))
    )
    (net (code "15") (name "/LAMP2") (class "Default")
      (node (ref "U21") (pin "12") (pinfunction "Q8_12") (pintype "tri_state"))
    )
    (net (code "16") (name "/LED_OE") (class "Default")
      (node (ref "U19") (pin "1") (pinfunction "~{OE}_1") (pintype "input"))
      (node (ref "U20") (pin "1") (pinfunction "~{OE}_1") (pintype "input"))
      (node (ref "U21") (pin "1") (pinfunction "~{OE}_1") (pintype "input"))
    )
    (net (code "17") (name "GND") (class "Default")
      (node (ref "C47") (pin "2") (pinfunction "2_2") (pintype "passive"))
      (node (ref "C48") (pin "2") (pinfunction "2_2") (pintype "passive"))
      (node (ref "C49") (pin "2") (pinfunction "2_2") (pintype "passive"))
      (node (ref "Q22") (pin "2") (pinfunction "E_2") (pintype "passive"))
      (node (ref "Q23") (pin "2") (pinfunction "E_2") (pintype "passive"))
      (node (ref "Q24") (pin "2") (pinfunction "E_2") (pintype "passive"))
      (node (ref "Q28") (pin "2") (pinfunction "E_2") (pintype "passive"))
      (node (ref "Q29") (pin "2") (pinfunction "E_2") (pintype "passive"))
      (node (ref "Q30") (pin "2") (pinfunction "E_2") (pintype "passive"))
      (node (ref "Q34") (pin "2") (pinfunction "E_2") (pintype "passive"))
      (node (ref "Q35") (pin "2") (pinfunction "E_2") (pintype "passive"))
      (node (ref "Q36") (pin "2") (pinfunction "E_2") (pintype "passive"))
      (node (ref "Q40") (pin "2") (pinfunction "E_2") (pintype "passive"))
      (node (ref "Q41") (pin "2") (pinfunction "E_2") (pintype "passive"))
      (node (ref "Q42") (pin "2") (pinfunction "E_2") (pintype "passive"))
      (node (ref "Q46") (pin "2") (pinfunction "E_2") (pintype "passive"))
      (node (ref "Q47") (pin "2") (pinfunction "E_2") (pintype "passive"))
      (node (ref "Q48") (pin "2") (pinfunction "E_2") (pintype "passive"))
      (node (ref "Q52") (pin "2") (pinfunction "E_2") (pintype "passive"))
      (node (ref "Q53") (pin "2") (pinfunction "E_2") (pintype "passive"))
      (node (ref "Q54") (pin "2") (pinfunction "E_2") (pintype "passive"))
      (node (ref "Q58") (pin "2") (pinfunction "E_2") (pintype "passive"))
      (node (ref "Q59") (pin "2") (pinfunction "E_2") (pintype "passive"))
      (node (ref "Q60") (pin "2") (pinfunction "E_2") (pintype "passive"))
      (node (ref "U19") (pin "10") (pinfunction "GND_10") (pintype "power_in"))
      (node (ref "U20") (pin "10") (pinfunction "GND_10") (pintype "power_in"))
      (node (ref "U21") (pin "10") (pinfunction "GND_10") (pintype "power_in"))
    )
    (net (code "18") (name "Net-(DS1-K)") (class "Default")
      (node (ref "DS1") (pin "2") (pinfunction "K_2") (pintype "passive"))
      (node (ref "DS2") (pin "1") (pinfunction "A_1") (pintype "passive"))
    )
    (net (code "19") (name "Net-(DS2-K)") (class "Default")
      (node (ref "DS2") (pin "2") (pinfunction "K_2") (pintype "passive"))
      (node (ref "R111") (pin "2") (pinfunction "2_2") (pintype "passive"))
    )
    (net (code "20") (name "Net-(DS3-K)") (class "Default")
      (node (ref "DS3") (pin "2") (pinfunction "K_2") (pintype "passive"))
      (node (ref "DS4") (pin "1") (pinfunction "A_1") (pintype "passive"))
    )
    (net (code "21") (name "Net-(DS4-K)") (class "Default")
      (node (ref "DS4") (pin "2") (pinfunction "K_2") (pintype "passive"))
      (node (ref "R112") (pin "2") (pinfunction "2_2") (pintype "passive"))
    )
    (net (code "22") (name "Net-(DS5-K)") (class "Default")
      (node (ref "DS5") (pin "2") (pinfunction "K_2") (pintype "passive"))
      (node (ref "DS6") (pin "1") (pinfunction "A_1") (pintype "passive"))
    )
    (net (code "23") (name "Net-(DS6-K)") (class "Default")
      (node (ref "DS6") (pin "2") (pinfunction "K_2") (pintype "passive"))
      (node (ref "R113") (pin "2") (pinfunction "2_2") (pintype "passive"))
    )
    (net (code "24") (name "Net-(DS13-K)") (class "Default")
      (node (ref "DS13") (pin "2") (pinfunction "K_2") (pintype "passive"))
      (node (ref "DS14") (pin "1") (pinfunction "A_1") (pintype "passive"))
    )
    (net (code "25") (name "Net-(DS14-K)") (class "Default")
      (node (ref "DS14") (pin "2") (pinfunction "K_2") (pintype "passive"))
      (node (ref "R117") (pin "2") (pinfunction "2_2") (pintype "passive"))
    )
    (net (code "26") (name "Net-(DS15-K)") (class "Default")
      (node (ref "DS15") (pin "2") (pinfunction "K_2") (pintype "passive"))
      (node (ref "DS16") (pin "1") (pinfunction "A_1") (pintype "passive"))
    )
    (net (code "27") (name "Net-(DS16-K)") (class "Default")
      (node (ref "DS16") (pin "2") (pinfunction "K_2") (pintype "passive"))
      (node (ref "R118") (pin "2") (pinfunction "2_2") (pintype "passive"))
    )
    (net (code "28") (name "Net-(DS17-K)") (class "Default")
      (node (ref "DS17") (pin "2") (pinfunction "K_2") (pintype "passive"))
      (node (ref "DS18") (pin "1") (pinfunction "A_1") (pintype "passive"))
    )
    (net (code "29") (name "Net-(DS18-K)") (class "Default")
      (node (ref "DS18") (pin "2") (pinfunction "K_2") (pintype "passive"))
      (node (ref "R119") (pin "2") (pinfunction "2_2") (pintype "passive"))
    )
    (net (code "30") (name "Net-(DS25-K)") (class "Default")
      (node (ref "DS25") (pin "2") (pinfunction "K_2") (pintype "passive"))
      (node (ref "DS26") (pin "1") (pinfunction "A_1") (pintype "passive"))
    )
    (net (code "31") (name "Net-(DS26-K)") (class "Default")
      (node (ref "DS26") (pin "2") (pinfunction "K_2") (pintype "passive"))
      (node (ref "R129") (pin "2") (pinfunction "2_2") (pintype "passive"))
    )
    (net (code "32") (name "Net-(DS27-K)") (class "Default")
      (node (ref "DS27") (pin "2") (pinfunction "K_2") (pintype "passive"))
      (node (ref "DS28") (pin "1") (pinfunction "A_1") (pintype "passive"))
    )
    (net (code "33") (name "Net-(DS28-K)") (class "Default")
      (node (ref "DS28") (pin "2") (pinfunction "K_2") (pintype "passive"))
      (node (ref "R130") (pin "2") (pinfunction "2_2") (pintype "passive"))
    )
    (net (code "34") (name "Net-(DS29-K)") (class "Default")
      (node (ref "DS29") (pin "2") (pinfunction "K_2") (pintype "passive"))
      (node (ref "DS30") (pin "1") (pinfunction "A_1") (pintype "passive"))
    )
    (net (code "35") (name "Net-(DS30-K)") (class "Default")
      (node (ref "DS30") (pin "2") (pinfunction "K_2") (pintype "passive"))
      (node (ref "R131") (pin "2") (pinfunction "2_2") (pintype "passive"))
    )
    (net (code "36") (name "Net-(DS37-K)") (class "Default")
      (node (ref "DS37") (pin "2") (pinfunction "K_2") (pintype "passive"))
      (node (ref "DS38") (pin "1") (pinfunction "A_1") (pintype "passive"))
    )
    (net (code "37") (name "Net-(DS38-K)") (class "Default")
      (node (ref "DS38") (pin "2") (pinfunction "K_2") (pintype "passive"))
      (node (ref "R135") (pin "2") (pinfunction "2_2") (pintype "passive"))
    )
    (net (code "38") (name "Net-(DS39-K)") (class "Default")
      (node (ref "DS39") (pin "2") (pinfunction "K_2") (pintype "passive"))
      (node (ref "DS40") (pin "1") (pinfunction "A_1") (pintype "passive"))
    )
    (net (code "39") (name "Net-(DS40-K)") (class "Default")
      (node (ref "DS40") (pin "2") (pinfunction "K_2") (pintype "passive"))
      (node (ref "R136") (pin "2") (pinfunction "2_2") (pintype "passive"))
    )
    (net (code "40") (name "Net-(DS41-K)") (class "Default")
      (node (ref "DS41") (pin "2") (pinfunction "K_2") (pintype "passive"))
      (node (ref "DS42") (pin "1") (pinfunction "A_1") (pintype "passive"))
    )
    (net (code "41") (name "Net-(DS42-K)") (class "Default")
      (node (ref "DS42") (pin "2") (pinfunction "K_2") (pintype "passive"))
      (node (ref "R137") (pin "2") (pinfunction "2_2") (pintype "passive"))
    )
    (net (code "42") (name "Net-(DS49-K)") (class "Default")
      (node (ref "DS49") (pin "2") (pinfunction "K_2") (pintype "passive"))
      (node (ref "DS50") (pin "1") (pinfunction "A_1") (pintype "passive"))
    )
    (net (code "43") (name "Net-(DS50-K)") (class "Default")
      (node (ref "DS50") (pin "2") (pinfunction "K_2") (pintype "passive"))
      (node (ref "R147") (pin "2") (pinfunction "2_2") (pintype "passive"))
    )
    (net (code "44") (name "Net-(DS51-K)") (class "Default")
      (node (ref "DS51") (pin "2") (pinfunction "K_2") (pintype "passive"))
      (node (ref "DS52") (pin "1") (pinfunction "A_1") (pintype "passive"))
    )
    (net (code "45") (name "Net-(DS52-K)") (class "Default")
      (node (ref "DS52") (pin "2") (pinfunction "K_2") (pintype "passive"))
      (node (ref "R148") (pin "2") (pinfunction "2_2") (pintype "passive"))
    )
    (net (code "46") (name "Net-(DS53-K)") (class "Default")
      (node (ref "DS53") (pin "2") (pinfunction "K_2") (pintype "passive"))
      (node (ref "DS54") (pin "1") (pinfunction "A_1") (pintype "passive"))
    )
    (net (code "47") (name "Net-(DS54-K)") (class "Default")
      (node (ref "DS54") (pin "2") (pinfunction "K_2") (pintype "passive"))
      (node (ref "R149") (pin "2") (pinfunction "2_2") (pintype "passive"))
    )
    (net (code "48") (name "Net-(DS61-K)") (class "Default")
      (node (ref "DS61") (pin "2") (pinfunction "K_2") (pintype "passive"))
      (node (ref "DS62") (pin "1") (pinfunction "A_1") (pintype "passive"))
    )
    (net (code "49") (name "Net-(DS62-K)") (class "Default")
      (node (ref "DS62") (pin "2") (pinfunction "K_2") (pintype "passive"))
      (node (ref "R153") (pin "2") (pinfunction "2_2") (pintype "passive"))
    )
    (net (code "50") (name "Net-(DS63-K)") (class "Default")
      (node (ref "DS63") (pin "2") (pinfunction "K_2") (pintype "passive"))
      (node (ref "DS64") (pin "1") (pinfunction "A_1") (pintype "passive"))
    )
    (net (code "51") (name "Net-(DS64-K)") (class "Default")
      (node (ref "DS64") (pin "2") (pinfunction "K_2") (pintype "passive"))
      (node (ref "R154") (pin "2") (pinfunction "2_2") (pintype "passive"))
    )
    (net (code "52") (name "Net-(DS65-K)") (class "Default")
      (node (ref "DS65") (pin "2") (pinfunction "K_2") (pintype "passive"))
      (node (ref "DS66") (pin "1") (pinfunction "A_1") (pintype "passive"))
    )
    (net (code "53") (name "Net-(DS66-K)") (class "Default")
      (node (ref "DS66") (pin "2") (pinfunction "K_2") (pintype "passive"))
      (node (ref "R155") (pin "2") (pinfunction "2_2") (pintype "passive"))
    )
    (net (code "54") (name "Net-(DS73-K)") (class "Default")
      (node (ref "DS73") (pin "2") (pinfunction "K_2") (pintype "passive"))
      (node (ref "DS74") (pin "1") (pinfunction "A_1") (pintype "passive"))
    )
    (net (code "55") (name "Net-(DS74-K)") (class "Default")
      (node (ref "DS74") (pin "2") (pinfunction "K_2") (pintype "passive"))
      (node (ref "R165") (pin "2") (pinfunction "2_2") (pintype "passive"))
    )
    (net (code "56") (name "Net-(DS75-K)") (class "Default")
      (node (ref "DS75") (pin "2") (pinfunction "K_2") (pintype "passive"))
      (node (ref "DS76") (pin "1") (pinfunction "A_1") (pintype "passive"))
    )
    (net (code "57") (name "Net-(DS76-K)") (class "Default")
      (node (ref "DS76") (pin "2") (pinfunction "K_2") (pintype "passive"))
      (node (ref "R166") (pin "2") (pinfunction "2_2") (pintype "passive"))
    )
    (net (code "58") (name "Net-(DS77-K)") (class "Default")
      (node (ref "DS77") (pin "2") (pinfunction "K_2") (pintype "passive"))
      (node (ref "DS78") (pin "1") (pinfunction "A_1") (pintype "passive"))
    )
    (net (code "59") (name "Net-(DS78-K)") (class "Default")
      (node (ref "DS78") (pin "2") (pinfunction "K_2") (pintype "passive"))
      (node (ref "R167") (pin "2") (pinfunction "2_2") (pintype "passive"))
    )
    (net (code "60") (name "Net-(DS85-K)") (class "Default")
      (node (ref "DS85") (pin "2") (pinfunction "K_2") (pintype "passive"))
      (node (ref "DS86") (pin "1") (pinfunction "A_1") (pintype "passive"))
    )
    (net (code "61") (name "Net-(DS86-K)") (class "Default")
      (node (ref "DS86") (pin "2") (pinfunction "K_2") (pintype "passive"))
      (node (ref "R171") (pin "2") (pinfunction "2_2") (pintype "passive"))
    )
    (net (code "62") (name "Net-(DS87-K)") (class "Default")
      (node (ref "DS87") (pin "2") (pinfunction "K_2") (pintype "passive"))
      (node (ref "DS88") (pin "1") (pinfunction "A_1") (pintype "passive"))
    )
    (net (code "63") (name "Net-(DS88-K)") (class "Default")
      (node (ref "DS88") (pin "2") (pinfunction "K_2") (pintype "passive"))
      (node (ref "R172") (pin "2") (pinfunction "2_2") (pintype "passive"))
    )
    (net (code "64") (name "Net-(DS89-K)") (class "Default")
      (node (ref "DS89") (pin "2") (pinfunction "K_2") (pintype "passive"))
      (node (ref "DS90") (pin "1") (pinfunction "A_1") (pintype "passive"))
    )
    (net (code "65") (name "Net-(DS90-K)") (class "Default")
      (node (ref "DS90") (pin "2") (pinfunction "K_2") (pintype "passive"))
      (node (ref "R173") (pin "2") (pinfunction "2_2") (pintype "passive"))
    )
    (net (code "66") (name "Net-(DS97-K)") (class "Default")
      (node (ref "DS97") (pin "2") (pinfunction "K_2") (pintype "passive"))
      (node (ref "DS98") (pin "1") (pinfunction "A_1") (pintype "passive"))
    )
    (net (code "67") (name "Net-(DS98-K)") (class "Default")
      (node (ref "DS98") (pin "2") (pinfunction "K_2") (pintype "passive"))
      (node (ref "R183") (pin "2") (pinfunction "2_2") (pintype "passive"))
    )
    (net (code "68") (name "Net-(DS100-A)") (class "Default")
      (node (ref "DS100") (pin "1") (pinfunction "A_1") (pintype "passive"))
      (node (ref "DS99") (pin "2") (pinfunction "K_2") (pintype "passive"))
    )
    (net (code "69") (name "Net-(DS100-K)") (class "Default")
      (node (ref "DS100") (pin "2") (pinfunction "K_2") (pintype "passive"))
      (node (ref "R184") (pin "2") (pinfunction "2_2") (pintype "passive"))
    )
    (net (code "70") (name "Net-(DS101-K)") (class "Default")
      (node (ref "DS101") (pin "2") (pinfunction "K_2") (pintype "passive"))
      (node (ref "DS102") (pin "1") (pinfunction "A_1") (pintype "passive"))
    )
    (net (code "71") (name "Net-(DS102-K)") (class "Default")
      (node (ref "DS102") (pin "2") (pinfunction "K_2") (pintype "passive"))
      (node (ref "R185") (pin "2") (pinfunction "2_2") (pintype "passive"))
    )
    (net (code "72") (name "Net-(DS109-K)") (class "Default")
      (node (ref "DS109") (pin "2") (pinfunction "K_2") (pintype "passive"))
      (node (ref "DS110") (pin "1") (pinfunction "A_1") (pintype "passive"))
    )
    (net (code "73") (name "Net-(DS110-K)") (class "Default")
      (node (ref "DS110") (pin "2") (pinfunction "K_2") (pintype "passive"))
      (node (ref "R189") (pin "2") (pinfunction "2_2") (pintype "passive"))
    )
    (net (code "74") (name "Net-(DS111-K)") (class "Default")
      (node (ref "DS111") (pin "2") (pinfunction "K_2") (pintype "passive"))
      (node (ref "DS112") (pin "1") (pinfunction "A_1") (pintype "passive"))
    )
    (net (code "75") (name "Net-(DS112-K)") (class "Default")
      (node (ref "DS112") (pin "2") (pinfunction "K_2") (pintype "passive"))
      (node (ref "R190") (pin "2") (pinfunction "2_2") (pintype "passive"))
    )
    (net (code "76") (name "Net-(DS113-K)") (class "Default")
      (node (ref "DS113") (pin "2") (pinfunction "K_2") (pintype "passive"))
      (node (ref "DS114") (pin "1") (pinfunction "A_1") (pintype "passive"))
    )
    (net (code "77") (name "Net-(DS114-K)") (class "Default")
      (node (ref "DS114") (pin "2") (pinfunction "K_2") (pintype "passive"))
      (node (ref "R191") (pin "2") (pinfunction "2_2") (pintype "passive"))
    )
    (net (code "78") (name "Net-(DS121-K)") (class "Default")
      (node (ref "DS121") (pin "2") (pinfunction "K_2") (pintype "passive"))
      (node (ref "DS122") (pin "1") (pinfunction "A_1") (pintype "passive"))
    )
    (net (code "79") (name "Net-(DS122-K)") (class "Default")
      (node (ref "DS122") (pin "2") (pinfunction "K_2") (pintype "passive"))
      (node (ref "R201") (pin "2") (pinfunction "2_2") (pintype "passive"))
    )
    (net (code "80") (name "Net-(DS123-K)") (class "Default")
      (node (ref "DS123") (pin "2") (pinfunction "K_2") (pintype "passive"))
      (node (ref "DS124") (pin "1") (pinfunction "A_1") (pintype "passive"))
    )
    (net (code "81") (name "Net-(DS124-K)") (class "Default")
      (node (ref "DS124") (pin "2") (pinfunction "K_2") (pintype "passive"))
      (node (ref "R202") (pin "2") (pinfunction "2_2") (pintype "passive"))
    )
    (net (code "82") (name "Net-(DS125-K)") (class "Default")
      (node (ref "DS125") (pin "2") (pinfunction "K_2") (pintype "passive"))
      (node (ref "DS126") (pin "1") (pinfunction "A_1") (pintype "passive"))
    )
    (net (code "83") (name "Net-(DS126-K)") (class "Default")
      (node (ref "DS126") (pin "2") (pinfunction "K_2") (pintype "passive"))
      (node (ref "R203") (pin "2") (pinfunction "2_2") (pintype "passive"))
    )
    (net (code "84") (name "Net-(DS133-K)") (class "Default")
      (node (ref "DS133") (pin "2") (pinfunction "K_2") (pintype "passive"))
      (node (ref "DS134") (pin "1") (pinfunction "A_1") (pintype "passive"))
    )
    (net (code "85") (name "Net-(DS134-K)") (class "Default")
      (node (ref "DS134") (pin "2") (pinfunction "K_2") (pintype "passive"))
      (node (ref "R207") (pin "2") (pinfunction "2_2") (pintype "passive"))
    )
    (net (code "86") (name "Net-(DS135-K)") (class "Default")
      (node (ref "DS135") (pin "2") (pinfunction "K_2") (pintype "passive"))
      (node (ref "DS136") (pin "1") (pinfunction "A_1") (pintype "passive"))
    )
    (net (code "87") (name "Net-(DS136-K)") (class "Default")
      (node (ref "DS136") (pin "2") (pinfunction "K_2") (pintype "passive"))
      (node (ref "R208") (pin "2") (pinfunction "2_2") (pintype "passive"))
    )
    (net (code "88") (name "Net-(DS137-K)") (class "Default")
      (node (ref "DS137") (pin "2") (pinfunction "K_2") (pintype "passive"))
      (node (ref "DS138") (pin "1") (pinfunction "A_1") (pintype "passive"))
    )
    (net (code "89") (name "Net-(DS138-K)") (class "Default")
      (node (ref "DS138") (pin "2") (pinfunction "K_2") (pintype "passive"))
      (node (ref "R209") (pin "2") (pinfunction "2_2") (pintype "passive"))
    )
    (net (code "90") (name "Net-(DS145-K)") (class "Default")
      (node (ref "DS145") (pin "2") (pinfunction "K_2") (pintype "passive"))
      (node (ref "DS146") (pin "1") (pinfunction "A_1") (pintype "passive"))
    )
    (net (code "91") (name "Net-(DS146-K)") (class "Default")
      (node (ref "DS146") (pin "2") (pinfunction "K_2") (pintype "passive"))
      (node (ref "R219") (pin "2") (pinfunction "2_2") (pintype "passive"))
    )
    (net (code "92") (name "Net-(DS147-K)") (class "Default")
      (node (ref "DS147") (pin "2") (pinfunction "K_2") (pintype "passive"))
      (node (ref "DS148") (pin "1") (pinfunction "A_1") (pintype "passive"))
    )
    (net (code "93") (name "Net-(DS148-K)") (class "Default")
      (node (ref "DS148") (pin "2") (pinfunction "K_2") (pintype "passive"))
      (node (ref "R220") (pin "2") (pinfunction "2_2") (pintype "passive"))
    )
    (net (code "94") (name "Net-(DS149-K)") (class "Default")
      (node (ref "DS149") (pin "2") (pinfunction "K_2") (pintype "passive"))
      (node (ref "DS150") (pin "1") (pinfunction "A_1") (pintype "passive"))
    )
    (net (code "95") (name "Net-(DS150-K)") (class "Default")
      (node (ref "DS150") (pin "2") (pinfunction "K_2") (pintype "passive"))
      (node (ref "R221") (pin "2") (pinfunction "2_2") (pintype "passive"))
    )
    (net (code "96") (name "Net-(DS157-K)") (class "Default")
      (node (ref "DS157") (pin "2") (pinfunction "K_2") (pintype "passive"))
      (node (ref "DS158") (pin "1") (pinfunction "A_1") (pintype "passive"))
    )
    (net (code "97") (name "Net-(DS158-K)") (class "Default")
      (node (ref "DS158") (pin "2") (pinfunction "K_2") (pintype "passive"))
      (node (ref "R225") (pin "2") (pinfunction "2_2") (pintype "passive"))
    )
    (net (code "98") (name "Net-(DS159-K)") (class "Default")
      (node (ref "DS159") (pin "2") (pinfunction "K_2") (pintype "passive"))
      (node (ref "DS160") (pin "1") (pinfunction "A_1") (pintype "passive"))
    )
    (net (code "99") (name "Net-(DS160-K)") (class "Default")
      (node (ref "DS160") (pin "2") (pinfunction "K_2") (pintype "passive"))
      (node (ref "R226") (pin "2") (pinfunction "2_2") (pintype "passive"))
    )
    (net (code "100") (name "Net-(DS161-K)") (class "Default")
      (node (ref "DS161") (pin "2") (pinfunction "K_2") (pintype "passive"))
      (node (ref "DS162") (pin "1") (pinfunction "A_1") (pintype "passive"))
    )
    (net (code "101") (name "Net-(DS162-K)") (class "Default")
      (node (ref "DS162") (pin "2") (pinfunction "K_2") (pintype "passive"))
      (node (ref "R227") (pin "2") (pinfunction "2_2") (pintype "passive"))
    )
    (net (code "102") (name "Net-(Q22-B)") (class "Default")
      (node (ref "Q22") (pin "1") (pinfunction "B_1") (pintype "passive"))
      (node (ref "R105") (pin "2") (pinfunction "2_2") (pintype "passive"))
    )
    (net (code "103") (name "Net-(Q22-C)") (class "Default")
      (node (ref "Q22") (pin "3") (pinfunction "C_3") (pintype "passive"))
      (node (ref "R111") (pin "1") (pinfunction "1_1") (pintype "passive"))
      (node (ref "R117") (pin "1") (pinfunction "1_1") (pintype "passive"))
    )
    (net (code "104") (name "Net-(Q23-B)") (class "Default")
      (node (ref "Q23") (pin "1") (pinfunction "B_1") (pintype "passive"))
      (node (ref "R106") (pin "2") (pinfunction "2_2") (pintype "passive"))
    )
    (net (code "105") (name "Net-(Q23-C)") (class "Default")
      (node (ref "Q23") (pin "3") (pinfunction "C_3") (pintype "passive"))
      (node (ref "R112") (pin "1") (pinfunction "1_1") (pintype "passive"))
      (node (ref "R118") (pin "1") (pinfunction "1_1") (pintype "passive"))
    )
    (net (code "106") (name "Net-(Q24-B)") (class "Default")
      (node (ref "Q24") (pin "1") (pinfunction "B_1") (pintype "passive"))
      (node (ref "R107") (pin "2") (pinfunction "2_2") (pintype "passive"))
    )
    (net (code "107") (name "Net-(Q24-C)") (class "Default")
      (node (ref "Q24") (pin "3") (pinfunction "C_3") (pintype "passive"))
      (node (ref "R113") (pin "1") (pinfunction "1_1") (pintype "passive"))
      (node (ref "R119") (pin "1") (pinfunction "1_1") (pintype "passive"))
    )
    (net (code "108") (name "Net-(Q28-B)") (class "Default")
      (node (ref "Q28") (pin "1") (pinfunction "B_1") (pintype "passive"))
      (node (ref "R123") (pin "2") (pinfunction "2_2") (pintype "passive"))
    )
    (net (code "109") (name "Net-(Q28-C)") (class "Default")
      (node (ref "Q28") (pin "3") (pinfunction "C_3") (pintype "passive"))
      (node (ref "R129") (pin "1") (pinfunction "1_1") (pintype "passive"))
      (node (ref "R135") (pin "1") (pinfunction "1_1") (pintype "passive"))
    )
    (net (code "110") (name "Net-(Q29-B)") (class "Default")
      (node (ref "Q29") (pin "1") (pinfunction "B_1") (pintype "passive"))
      (node (ref "R124") (pin "2") (pinfunction "2_2") (pintype "passive"))
    )
    (net (code "111") (name "Net-(Q29-C)") (class "Default")
      (node (ref "Q29") (pin "3") (pinfunction "C_3") (pintype "passive"))
      (node (ref "R130") (pin "1") (pinfunction "1_1") (pintype "passive"))
      (node (ref "R136") (pin "1") (pinfunction "1_1") (pintype "passive"))
    )
    (net (code "112") (name "Net-(Q30-B)") (class "Default")
      (node (ref "Q30") (pin "1") (pinfunction "B_1") (pintype "passive"))
      (node (ref "R125") (pin "2") (pinfunction "2_2") (pintype "passive"))
    )
    (net (code "113") (name "Net-(Q30-C)") (class "Default")
      (node (ref "Q30") (pin "3") (pinfunction "C_3") (pintype "passive"))
      (node (ref "R131") (pin "1") (pinfunction "1_1") (pintype "passive"))
      (node (ref "R137") (pin "1") (pinfunction "1_1") (pintype "passive"))
    )
    (net (code "114") (name "Net-(Q34-B)") (class "Default")
      (node (ref "Q34") (pin "1") (pinfunction "B_1") (pintype "passive"))
      (node (ref "R141") (pin "2") (pinfunction "2_2") (pintype "passive"))
    )
    (net (code "115") (name "Net-(Q34-C)") (class "Default")
      (node (ref "Q34") (pin "3") (pinfunction "C_3") (pintype "passive"))
      (node (ref "R147") (pin "1") (pinfunction "1_1") (pintype "passive"))
      (node (ref "R153") (pin "1") (pinfunction "1_1") (pintype "passive"))
    )
    (net (code "116") (name "Net-(Q35-B)") (class "Default")
      (node (ref "Q35") (pin "1") (pinfunction "B_1") (pintype "passive"))
      (node (ref "R142") (pin "2") (pinfunction "2_2") (pintype "passive"))
    )
    (net (code "117") (name "Net-(Q35-C)") (class "Default")
      (node (ref "Q35") (pin "3") (pinfunction "C_3") (pintype "passive"))
      (node (ref "R148") (pin "1") (pinfunction "1_1") (pintype "passive"))
      (node (ref "R154") (pin "1") (pinfunction "1_1") (pintype "passive"))
    )
    (net (code "118") (name "Net-(Q36-B)") (class "Default")
      (node (ref "Q36") (pin "1") (pinfunction "B_1") (pintype "passive"))
      (node (ref "R143") (pin "2") (pinfunction "2_2") (pintype "passive"))
    )
    (net (code "119") (name "Net-(Q36-C)") (class "Default")
      (node (ref "Q36") (pin "3") (pinfunction "C_3") (pintype "passive"))
      (node (ref "R149") (pin "1") (pinfunction "1_1") (pintype "passive"))
      (node (ref "R155") (pin "1") (pinfunction "1_1") (pintype "passive"))
    )
    (net (code "120") (name "Net-(Q40-B)") (class "Default")
      (node (ref "Q40") (pin "1") (pinfunction "B_1") (pintype "passive"))
      (node (ref "R159") (pin "2") (pinfunction "2_2") (pintype "passive"))
    )
    (net (code "121") (name "Net-(Q40-C)") (class "Default")
      (node (ref "Q40") (pin "3") (pinfunction "C_3") (pintype "passive"))
      (node (ref "R165") (pin "1") (pinfunction "1_1") (pintype "passive"))
      (node (ref "R171") (pin "1") (pinfunction "1_1") (pintype "passive"))
    )
    (net (code "122") (name "Net-(Q41-B)") (class "Default")
      (node (ref "Q41") (pin "1") (pinfunction "B_1") (pintype "passive"))
      (node (ref "R160") (pin "2") (pinfunction "2_2") (pintype "passive"))
    )
    (net (code "123") (name "Net-(Q41-C)") (class "Default")
      (node (ref "Q41") (pin "3") (pinfunction "C_3") (pintype "passive"))
      (node (ref "R166") (pin "1") (pinfunction "1_1") (pintype "passive"))
      (node (ref "R172") (pin "1") (pinfunction "1_1") (pintype "passive"))
    )
    (net (code "124") (name "Net-(Q42-B)") (class "Default")
      (node (ref "Q42") (pin "1") (pinfunction "B_1") (pintype "passive"))
      (node (ref "R161") (pin "2") (pinfunction "2_2") (pintype "passive"))
    )
    (net (code "125") (name "Net-(Q42-C)") (class "Default")
      (node (ref "Q42") (pin "3") (pinfunction "C_3") (pintype "passive"))
      (node (ref "R167") (pin "1") (pinfunction "1_1") (pintype "passive"))
      (node (ref "R173") (pin "1") (pinfunction "1_1") (pintype "passive"))
    )
    (net (code "126") (name "Net-(Q46-B)") (class "Default")
      (node (ref "Q46") (pin "1") (pinfunction "B_1") (pintype "passive"))
      (node (ref "R177") (pin "2") (pinfunction "2_2") (pintype "passive"))
    )
    (net (code "127") (name "Net-(Q46-C)") (class "Default")
      (node (ref "Q46") (pin "3") (pinfunction "C_3") (pintype "passive"))
      (node (ref "R183") (pin "1") (pinfunction "1_1") (pintype "passive"))
      (node (ref "R189") (pin "1") (pinfunction "1_1") (pintype "passive"))
    )
    (net (code "128") (name "Net-(Q47-B)") (class "Default")
      (node (ref "Q47") (pin "1") (pinfunction "B_1") (pintype "passive"))
      (node (ref "R178") (pin "2") (pinfunction "2_2") (pintype "passive"))
    )
    (net (code "129") (name "Net-(Q47-C)") (class "Default")
      (node (ref "Q47") (pin "3") (pinfunction "C_3") (pintype "passive"))
      (node (ref "R184") (pin "1") (pinfunction "1_1") (pintype "passive"))
      (node (ref "R190") (pin "1") (pinfunction "1_1") (pintype "passive"))
    )
    (net (code "130") (name "Net-(Q48-B)") (class "Default")
      (node (ref "Q48") (pin "1") (pinfunction "B_1") (pintype "passive"))
      (node (ref "R179") (pin "2") (pinfunction "2_2") (pintype "passive"))
    )
    (net (code "131") (name "Net-(Q48-C)") (class "Default")
      (node (ref "Q48") (pin "3") (pinfunction "C_3") (pintype "passive"))
      (node (ref "R185") (pin "1") (pinfunction "1_1") (pintype "passive"))
      (node (ref "R191") (pin "1") (pinfunction "1_1") (pintype "passive"))
    )
    (net (code "132") (name "Net-(Q52-B)") (class "Default")
      (node (ref "Q52") (pin "1") (pinfunction "B_1") (pintype "passive"))
      (node (ref "R195") (pin "2") (pinfunction "2_2") (pintype "passive"))
    )
    (net (code "133") (name "Net-(Q52-C)") (class "Default")
      (node (ref "Q52") (pin "3") (pinfunction "C_3") (pintype "passive"))
      (node (ref "R201") (pin "1") (pinfunction "1_1") (pintype "passive"))
      (node (ref "R207") (pin "1") (pinfunction "1_1") (pintype "passive"))
    )
    (net (code "134") (name "Net-(Q53-B)") (class "Default")
      (node (ref "Q53") (pin "1") (pinfunction "B_1") (pintype "passive"))
      (node (ref "R196") (pin "2") (pinfunction "2_2") (pintype "passive"))
    )
    (net (code "135") (name "Net-(Q53-C)") (class "Default")
      (node (ref "Q53") (pin "3") (pinfunction "C_3") (pintype "passive"))
      (node (ref "R202") (pin "1") (pinfunction "1_1") (pintype "passive"))
      (node (ref "R208") (pin "1") (pinfunction "1_1") (pintype "passive"))
    )
    (net (code "136") (name "Net-(Q54-B)") (class "Default")
      (node (ref "Q54") (pin "1") (pinfunction "B_1") (pintype "passive"))
      (node (ref "R197") (pin "2") (pinfunction "2_2") (pintype "passive"))
    )
    (net (code "137") (name "Net-(Q54-C)") (class "Default")
      (node (ref "Q54") (pin "3") (pinfunction "C_3") (pintype "passive"))
      (node (ref "R203") (pin "1") (pinfunction "1_1") (pintype "passive"))
      (node (ref "R209") (pin "1") (pinfunction "1_1") (pintype "passive"))
    )
    (net (code "138") (name "Net-(Q58-B)") (class "Default")
      (node (ref "Q58") (pin "1") (pinfunction "B_1") (pintype "passive"))
      (node (ref "R213") (pin "2") (pinfunction "2_2") (pintype "passive"))
    )
    (net (code "139") (name "Net-(Q58-C)") (class "Default")
      (node (ref "Q58") (pin "3") (pinfunction "C_3") (pintype "passive"))
      (node (ref "R219") (pin "1") (pinfunction "1_1") (pintype "passive"))
      (node (ref "R225") (pin "1") (pinfunction "1_1") (pintype "passive"))
    )
    (net (code "140") (name "Net-(Q59-B)") (class "Default")
      (node (ref "Q59") (pin "1") (pinfunction "B_1") (pintype "passive"))
      (node (ref "R214") (pin "2") (pinfunction "2_2") (pintype "passive"))
    )
    (net (code "141") (name "Net-(Q59-C)") (class "Default")
      (node (ref "Q59") (pin "3") (pinfunction "C_3") (pintype "passive"))
      (node (ref "R220") (pin "1") (pinfunction "1_1") (pintype "passive"))
      (node (ref "R226") (pin "1") (pinfunction "1_1") (pintype "passive"))
    )
    (net (code "142") (name "Net-(Q60-B)") (class "Default")
      (node (ref "Q60") (pin "1") (pinfunction "B_1") (pintype "passive"))
      (node (ref "R215") (pin "2") (pinfunction "2_2") (pintype "passive"))
    )
    (net (code "143") (name "Net-(Q60-C)") (class "Default")
      (node (ref "Q60") (pin "3") (pinfunction "C_3") (pintype "passive"))
      (node (ref "R221") (pin "1") (pinfunction "1_1") (pintype "passive"))
      (node (ref "R227") (pin "1") (pinfunction "1_1") (pintype "passive"))
    )
    (net (code "144") (name "Net-(U19-Q1)") (class "Default")
      (node (ref "R105") (pin "1") (pinfunction "1_1") (pintype "passive"))
      (node (ref "U19") (pin "19") (pinfunction "Q1_19") (pintype "tri_state"))
    )
    (net (code "145") (name "Net-(U19-Q2)") (class "Default")
      (node (ref "R123") (pin "1") (pinfunction "1_1") (pintype "passive"))
      (node (ref "U19") (pin "18") (pinfunction "Q2_18") (pintype "tri_state"))
    )
    (net (code "146") (name "Net-(U19-Q3)") (class "Default")
      (node (ref "R141") (pin "1") (pinfunction "1_1") (pintype "passive"))
      (node (ref "U19") (pin "17") (pinfunction "Q3_17") (pintype "tri_state"))
    )
    (net (code "147") (name "Net-(U19-Q4)") (class "Default")
      (node (ref "R159") (pin "1") (pinfunction "1_1") (pintype "passive"))
      (node (ref "U19") (pin "16") (pinfunction "Q4_16") (pintype "tri_state"))
    )
    (net (code "148") (name "Net-(U19-Q5)") (class "Default")
      (node (ref "R177") (pin "1") (pinfunction "1_1") (pintype "passive"))
      (node (ref "U19") (pin "15") (pinfunction "Q5_15") (pintype "tri_state"))
    )
    (net (code "149") (name "Net-(U19-Q6)") (class "Default")
      (node (ref "R195") (pin "1") (pinfunction "1_1") (pintype "passive"))
      (node (ref "U19") (pin "14") (pinfunction "Q6_14") (pintype "tri_state"))
    )
    (net (code "150") (name "Net-(U19-Q7)") (class "Default")
      (node (ref "R213") (pin "1") (pinfunction "1_1") (pintype "passive"))
      (node (ref "U19") (pin "13") (pinfunction "Q7_13") (pintype "tri_state"))
    )
    (net (code "151") (name "Net-(U20-Q1)") (class "Default")
      (node (ref "R106") (pin "1") (pinfunction "1_1") (pintype "passive"))
      (node (ref "U20") (pin "19") (pinfunction "Q1_19") (pintype "tri_state"))
    )
    (net (code "152") (name "Net-(U20-Q2)") (class "Default")
      (node (ref "R124") (pin "1") (pinfunction "1_1") (pintype "passive"))
      (node (ref "U20") (pin "18") (pinfunction "Q2_18") (pintype "tri_state"))
    )
    (net (code "153") (name "Net-(U20-Q3)") (class "Default")
      (node (ref "R142") (pin "1") (pinfunction "1_1") (pintype "passive"))
      (node (ref "U20") (pin "17") (pinfunction "Q3_17") (pintype "tri_state"))
    )
    (net (code "154") (name "Net-(U20-Q4)") (class "Default")
      (node (ref "R160") (pin "1") (pinfunction "1_1") (pintype "passive"))
      (node (ref "U20") (pin "16") (pinfunction "Q4_16") (pintype "tri_state"))
    )
    (net (code "155") (name "Net-(U20-Q5)") (class "Default")
      (node (ref "R178") (pin "1") (pinfunction "1_1") (pintype "passive"))
      (node (ref "U20") (pin "15") (pinfunction "Q5_15") (pintype "tri_state"))
    )
    (net (code "156") (name "Net-(U20-Q6)") (class "Default")
      (node (ref "R196") (pin "1") (pinfunction "1_1") (pintype "passive"))
      (node (ref "U20") (pin "14") (pinfunction "Q6_14") (pintype "tri_state"))
    )
    (net (code "157") (name "Net-(U20-Q7)") (class "Default")
      (node (ref "R214") (pin "1") (pinfunction "1_1") (pintype "passive"))
      (node (ref "U20") (pin "13") (pinfunction "Q7_13") (pintype "tri_state"))
    )
    (net (code "158") (name "Net-(U21-Q1)") (class "Default")
      (node (ref "R107") (pin "1") (pinfunction "1_1") (pintype "passive"))
      (node (ref "U21") (pin "19") (pinfunction "Q1_19") (pintype "tri_state"))
    )
    (net (code "159") (name "Net-(U21-Q2)") (class "Default")
      (node (ref "R125") (pin "1") (pinfunction "1_1") (pintype "passive"))
      (node (ref "U21") (pin "18") (pinfunction "Q2_18") (pintype "tri_state"))
    )
    (net (code "160") (name "Net-(U21-Q3)") (class "Default")
      (node (ref "R143") (pin "1") (pinfunction "1_1") (pintype "passive"))
      (node (ref "U21") (pin "17") (pinfunction "Q3_17") (pintype "tri_state"))
    )
    (net (code "161") (name "Net-(U21-Q4)") (class "Default")
      (node (ref "R161") (pin "1") (pinfunction "1_1") (pintype "passive"))
      (node (ref "U21") (pin "16") (pinfunction "Q4_16") (pintype "tri_state"))
    )
    (net (code "162") (name "Net-(U21-Q5)") (class "Default")
      (node (ref "R179") (pin "1") (pinfunction "1_1") (pintype "passive"))
      (node (ref "U21") (pin "15") (pinfunction "Q5_15") (pintype "tri_state"))
    )
    (net (code "163") (name "Net-(U21-Q6)") (class "Default")
      (node (ref "R197") (pin "1") (pinfunction "1_1") (pintype "passive"))
      (node (ref "U21") (pin "14") (pinfunction "Q6_14") (pintype "tri_state"))
    )
    (net (code "164") (name "Net-(U21-Q7)") (class "Default")
      (node (ref "R215") (pin "1") (pinfunction "1_1") (pintype "passive"))
      (node (ref "U21") (pin "13") (pinfunction "Q7_13") (pintype "tri_state"))
    )
    (net (code "165") (name "VCC") (class "Default")
      (node (ref "C47") (pin "1") (pinfunction "1_1") (pintype "passive"))
      (node (ref "C48") (pin "1") (pinfunction "1_1") (pintype "passive"))
      (node (ref "C49") (pin "1") (pinfunction "1_1") (pintype "passive"))
      (node (ref "U19") (pin "20") (pinfunction "VCC_20") (pintype "power_in"))
      (node (ref "U20") (pin "20") (pinfunction "VCC_20") (pintype "power_in"))
      (node (ref "U21") (pin "20") (pinfunction "VCC_20") (pintype "power_in"))
    )
  )
)
